# EP1C6T144I8N_2.net
KiCad netlist of a schematic drawn in Altium Designer
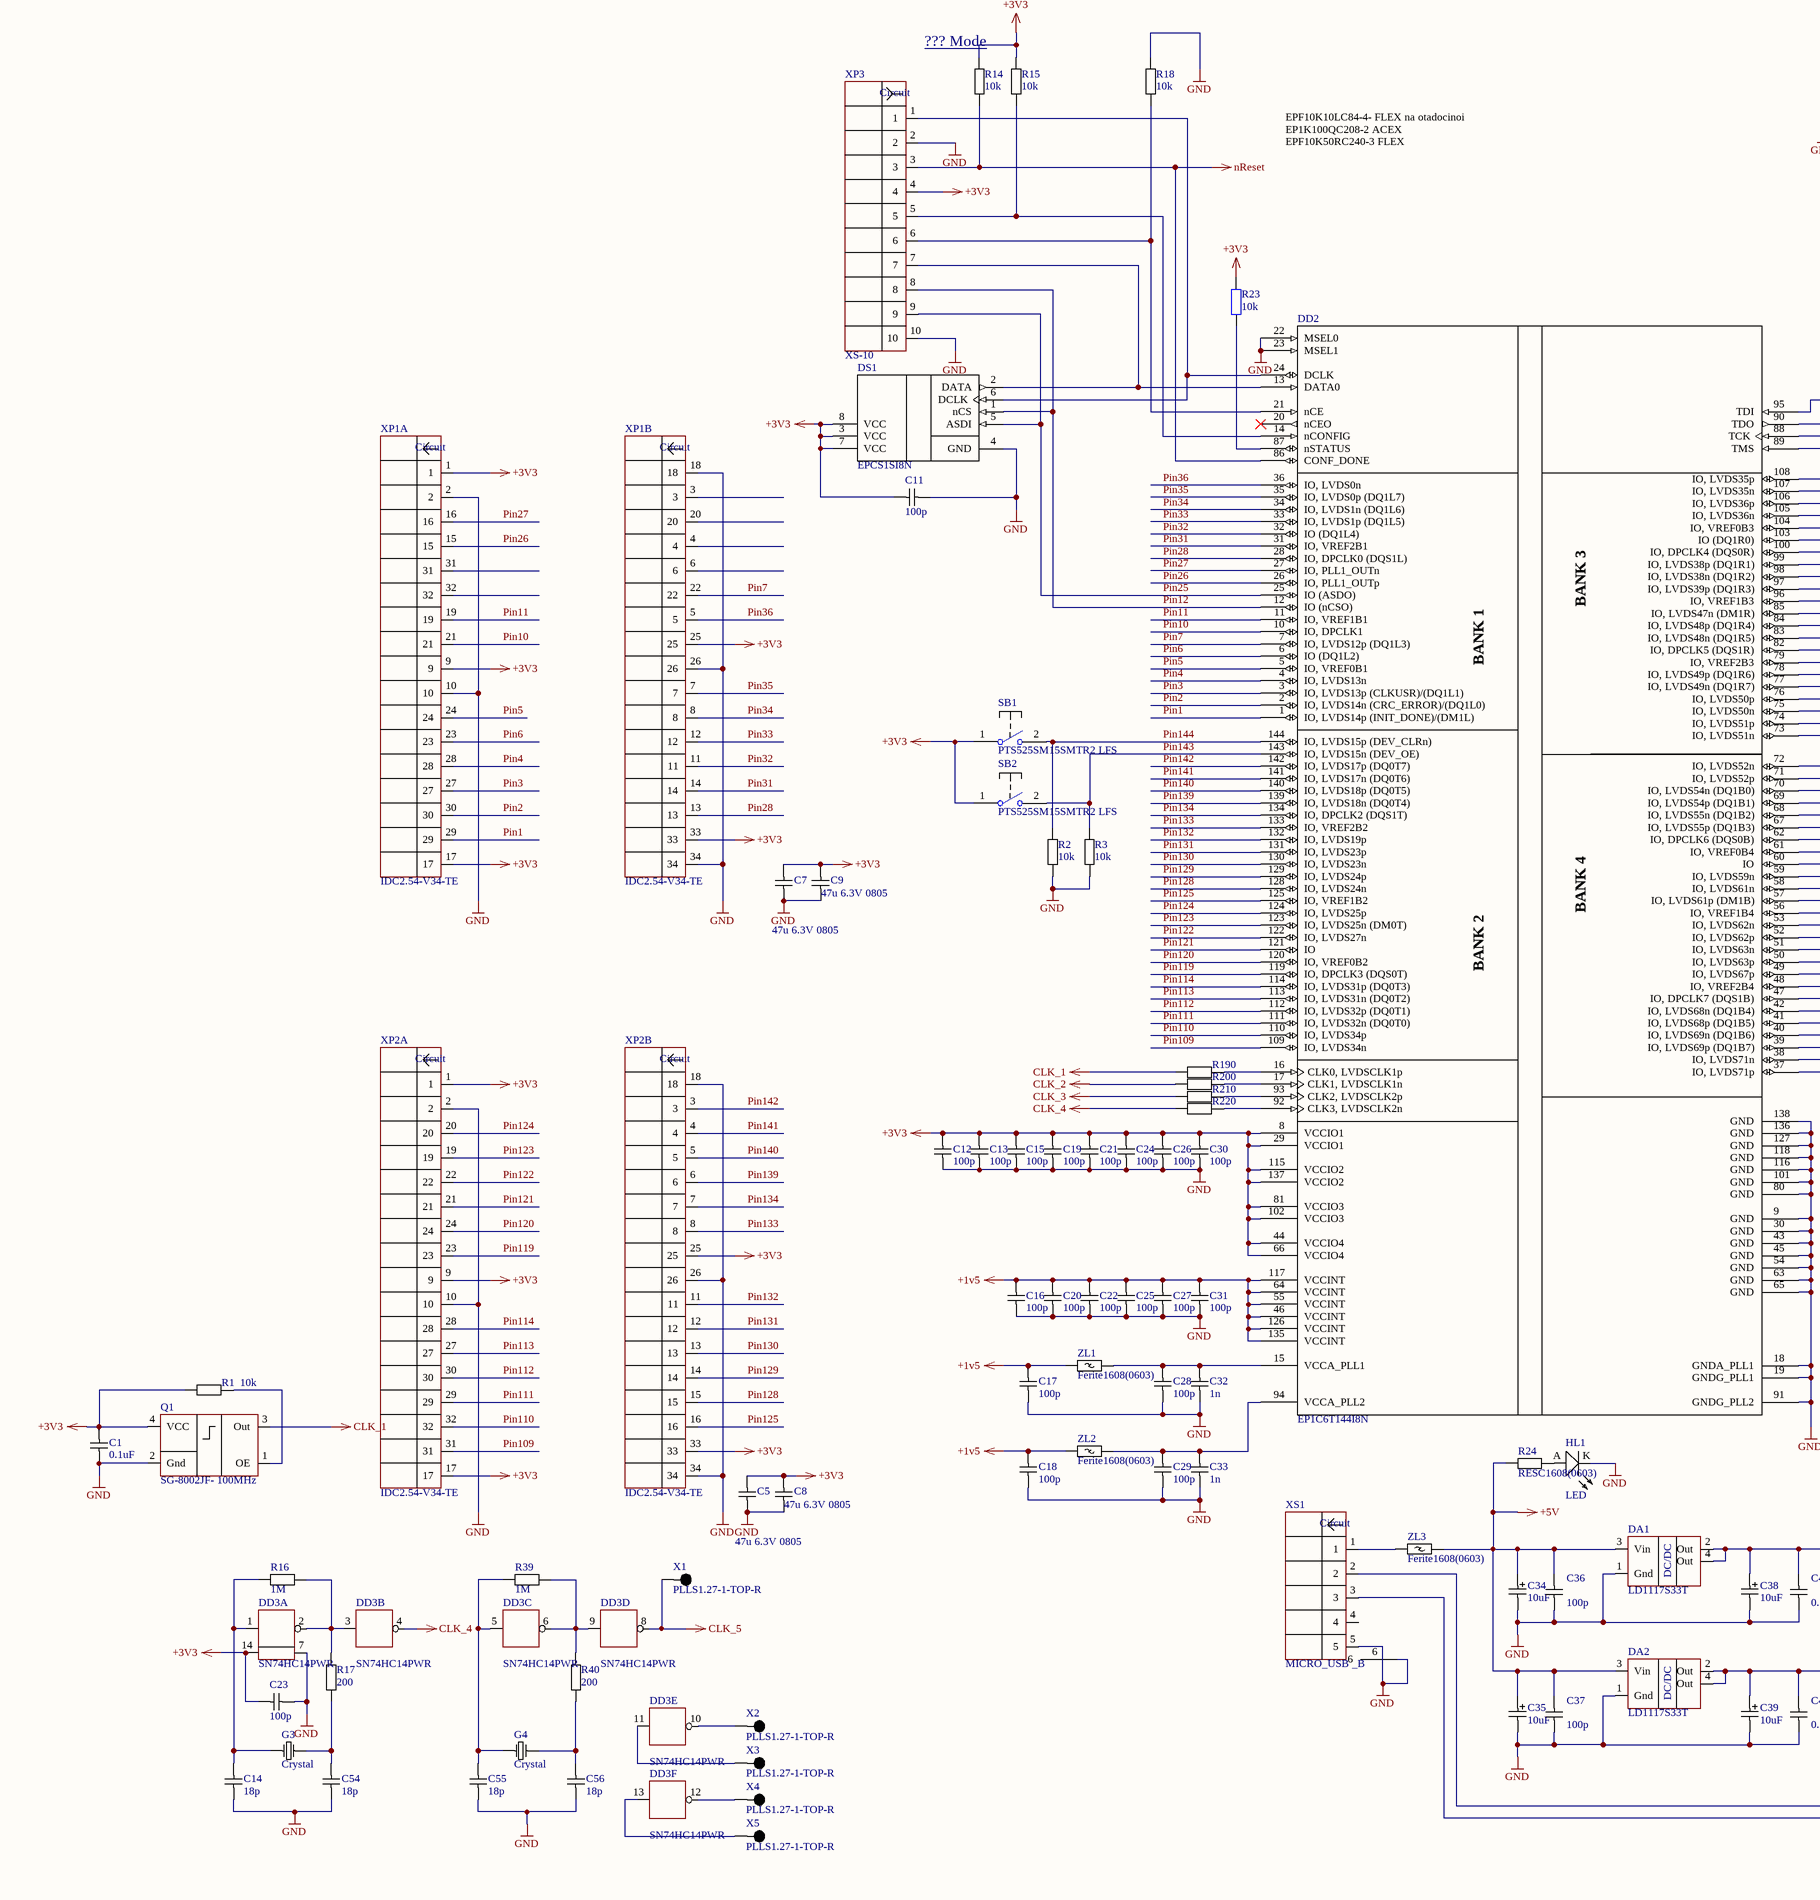
[diagram p0: EP1C6T144I8N (2).SchDoc, bottom left]
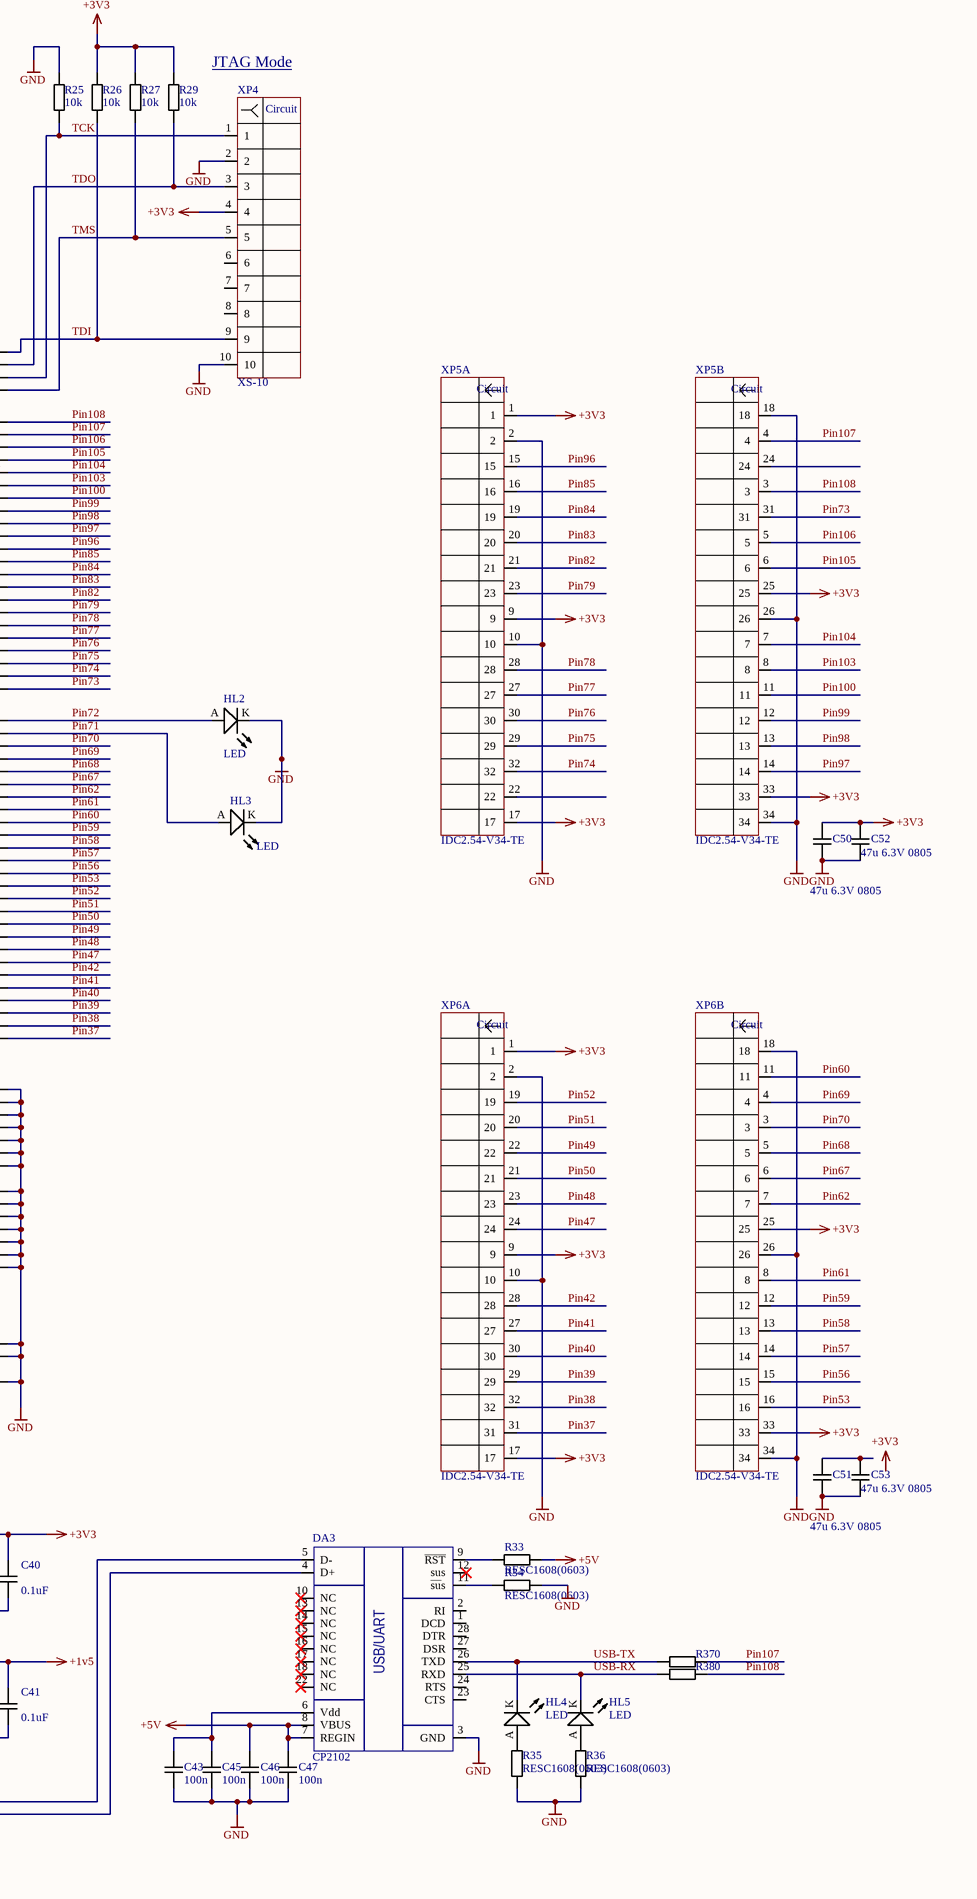
[diagram p1: EP1C6T144I8N (2).SchDoc, bottom right]

(export (version "E")
  (design (tool "Eeschema 10.0.6"))
  (components
    (comp (ref "C1")
      (value "0.1uF")
      (footprint "1005[0402]:CapKemet1005(0402)")
      (fields (field (name "PART NUMBER") "CAPC1005(0402)N") (field (name "DIGI-KEY PART NUMBER") "?"))
      (libsource (lib "ADdatabaseLibfile") (part "Cap"))
    )
    (comp (ref "C5")
      (value "47u 6.3V 0805")
      (footprint "CAPC2012(0805)N")
      (description "CAP CER 47UF 6.3V X5R 0805")
      (fields
        (field (name "PART NUMBER") "CAPC2012(0805)")
        (field (name "DIGI-KEY PART NUMBER") "490-13249-1-ND")
      )
      (libsource (lib "SssAccesDatbase") (part "Cap"))
    )
    (comp (ref "C7")
      (value "47u 6.3V 0805")
      (footprint "CAPC2012(0805)N")
      (description "CAP CER 47UF 6.3V X5R 0805")
      (fields
        (field (name "PART NUMBER") "CAPC2012(0805)")
        (field (name "DIGI-KEY PART NUMBER") "490-13249-1-ND")
      )
      (libsource (lib "SssAccesDatbase") (part "Cap"))
    )
    (comp (ref "C8")
      (value "47u 6.3V 0805")
      (footprint "CAPC2012(0805)N")
      (description "CAP CER 47UF 6.3V X5R 0805")
      (fields
        (field (name "PART NUMBER") "CAPC2012(0805)")
        (field (name "DIGI-KEY PART NUMBER") "490-13249-1-ND")
      )
      (libsource (lib "SssAccesDatbase") (part "Cap"))
    )
    (comp (ref "C9")
      (value "47u 6.3V 0805")
      (footprint "CAPC2012(0805)N")
      (description "CAP CER 47UF 6.3V X5R 0805")
      (fields
        (field (name "PART NUMBER") "CAPC2012(0805)")
        (field (name "DIGI-KEY PART NUMBER") "490-13249-1-ND")
      )
      (libsource (lib "SssAccesDatbase") (part "Cap"))
    )
    (comp (ref "C11")
      (value "100p")
      (footprint "1005[0402]:CapKemet1005(0402)")
      (fields (field (name "PART NUMBER") "CAPC1005(0402)N") (field (name "DIGI-KEY PART NUMBER") "?"))
      (libsource (lib "ADdatabaseLibfile") (part "Cap"))
    )
    (comp (ref "C12")
      (value "100p")
      (footprint "1005[0402]:CapKemet1005(0402)")
      (fields (field (name "PART NUMBER") "CAPC1005(0402)N") (field (name "DIGI-KEY PART NUMBER") "?"))
      (libsource (lib "ADdatabaseLibfile") (part "Cap"))
    )
    (comp (ref "C13")
      (value "100p")
      (footprint "1005[0402]:CapKemet1005(0402)")
      (fields (field (name "PART NUMBER") "CAPC1005(0402)N") (field (name "DIGI-KEY PART NUMBER") "?"))
      (libsource (lib "ADdatabaseLibfile") (part "Cap"))
    )
    (comp (ref "C14")
      (value "18p")
      (footprint "CAPC1608(0603)N")
      (description "?")
      (fields (field (name "PART NUMBER") "CAPC1608(0603)"))
      (libsource (lib "SssAccesDatbase") (part "Cap"))
    )
    (comp (ref "C15")
      (value "100p")
      (footprint "1005[0402]:CapKemet1005(0402)")
      (fields (field (name "PART NUMBER") "CAPC1005(0402)N") (field (name "DIGI-KEY PART NUMBER") "?"))
      (libsource (lib "ADdatabaseLibfile") (part "Cap"))
    )
    (comp (ref "C16")
      (value "100p")
      (footprint "1005[0402]:CapKemet1005(0402)")
      (fields (field (name "PART NUMBER") "CAPC1005(0402)N") (field (name "DIGI-KEY PART NUMBER") "?"))
      (libsource (lib "ADdatabaseLibfile") (part "Cap"))
    )
    (comp (ref "C17")
      (value "100p")
      (footprint "1005[0402]:CapKemet1005(0402)")
      (fields (field (name "PART NUMBER") "CAPC1005(0402)N") (field (name "DIGI-KEY PART NUMBER") "?"))
      (libsource (lib "ADdatabaseLibfile") (part "Cap"))
    )
    (comp (ref "C18")
      (value "100p")
      (footprint "1005[0402]:CapKemet1005(0402)")
      (fields (field (name "PART NUMBER") "CAPC1005(0402)N") (field (name "DIGI-KEY PART NUMBER") "?"))
      (libsource (lib "ADdatabaseLibfile") (part "Cap"))
    )
    (comp (ref "C19")
      (value "100p")
      (footprint "1005[0402]:CapKemet1005(0402)")
      (fields (field (name "PART NUMBER") "CAPC1005(0402)N") (field (name "DIGI-KEY PART NUMBER") "?"))
      (libsource (lib "ADdatabaseLibfile") (part "Cap"))
    )
    (comp (ref "C20")
      (value "100p")
      (footprint "1005[0402]:CapKemet1005(0402)")
      (fields (field (name "PART NUMBER") "CAPC1005(0402)N") (field (name "DIGI-KEY PART NUMBER") "?"))
      (libsource (lib "ADdatabaseLibfile") (part "Cap"))
    )
    (comp (ref "C21")
      (value "100p")
      (footprint "1005[0402]:CapKemet1005(0402)")
      (fields (field (name "PART NUMBER") "CAPC1005(0402)N") (field (name "DIGI-KEY PART NUMBER") "?"))
      (libsource (lib "ADdatabaseLibfile") (part "Cap"))
    )
    (comp (ref "C22")
      (value "100p")
      (footprint "1005[0402]:CapKemet1005(0402)")
      (fields (field (name "PART NUMBER") "CAPC1005(0402)N") (field (name "DIGI-KEY PART NUMBER") "?"))
      (libsource (lib "ADdatabaseLibfile") (part "Cap"))
    )
    (comp (ref "C23")
      (value "100p")
      (footprint "CAPC1608(0603)N")
      (description "?")
      (fields (field (name "PART NUMBER") "CAPC1608(0603)"))
      (libsource (lib "SssAccesDatbaseDYandex") (part "Cap"))
    )
    (comp (ref "C24")
      (value "100p")
      (footprint "1005[0402]:CapKemet1005(0402)")
      (fields (field (name "PART NUMBER") "CAPC1005(0402)N") (field (name "DIGI-KEY PART NUMBER") "?"))
      (libsource (lib "ADdatabaseLibfile") (part "Cap"))
    )
    (comp (ref "C25")
      (value "100p")
      (footprint "1005[0402]:CapKemet1005(0402)")
      (fields (field (name "PART NUMBER") "CAPC1005(0402)N") (field (name "DIGI-KEY PART NUMBER") "?"))
      (libsource (lib "ADdatabaseLibfile") (part "Cap"))
    )
    (comp (ref "C26")
      (value "100p")
      (footprint "1005[0402]:CapKemet1005(0402)")
      (fields (field (name "PART NUMBER") "CAPC1005(0402)N") (field (name "DIGI-KEY PART NUMBER") "?"))
      (libsource (lib "ADdatabaseLibfile") (part "Cap"))
    )
    (comp (ref "C27")
      (value "100p")
      (footprint "1005[0402]:CapKemet1005(0402)")
      (fields (field (name "PART NUMBER") "CAPC1005(0402)N") (field (name "DIGI-KEY PART NUMBER") "?"))
      (libsource (lib "ADdatabaseLibfile") (part "Cap"))
    )
    (comp (ref "C28")
      (value "100p")
      (footprint "1005[0402]:CapKemet1005(0402)")
      (fields (field (name "PART NUMBER") "CAPC1005(0402)N") (field (name "DIGI-KEY PART NUMBER") "?"))
      (libsource (lib "ADdatabaseLibfile") (part "Cap"))
    )
    (comp (ref "C29")
      (value "100p")
      (footprint "1005[0402]:CapKemet1005(0402)")
      (fields (field (name "PART NUMBER") "CAPC1005(0402)N") (field (name "DIGI-KEY PART NUMBER") "?"))
      (libsource (lib "ADdatabaseLibfile") (part "Cap"))
    )
    (comp (ref "C30")
      (value "100p")
      (footprint "1005[0402]:CapKemet1005(0402)")
      (fields (field (name "PART NUMBER") "CAPC1005(0402)N") (field (name "DIGI-KEY PART NUMBER") "?"))
      (libsource (lib "ADdatabaseLibfile") (part "Cap"))
    )
    (comp (ref "C31")
      (value "100p")
      (footprint "1005[0402]:CapKemet1005(0402)")
      (fields (field (name "PART NUMBER") "CAPC1005(0402)N") (field (name "DIGI-KEY PART NUMBER") "?"))
      (libsource (lib "ADdatabaseLibfile") (part "Cap"))
    )
    (comp (ref "C32")
      (value "1n")
      (footprint "1005[0402]:CapKemet1005(0402)")
      (fields (field (name "PART NUMBER") "CAPC1005(0402)N") (field (name "DIGI-KEY PART NUMBER") "?"))
      (libsource (lib "ADdatabaseLibfile") (part "Cap"))
    )
    (comp (ref "C33")
      (value "1n")
      (footprint "1005[0402]:CapKemet1005(0402)")
      (fields (field (name "PART NUMBER") "CAPC1005(0402)N") (field (name "DIGI-KEY PART NUMBER") "?"))
      (libsource (lib "ADdatabaseLibfile") (part "Cap"))
    )
    (comp (ref "C34")
      (value "10uF")
      (footprint "0402-A")
      (fields (field (name "PART NUMBER") "CapTantA"))
      (libsource (lib "ADdatabaseLibfile") (part "Cap Pol1"))
    )
    (comp (ref "C35")
      (value "10uF")
      (footprint "0402-A")
      (fields (field (name "PART NUMBER") "CapTantA"))
      (libsource (lib "ADdatabaseLibfile") (part "Cap Pol1"))
    )
    (comp (ref "C36")
      (value "100p")
      (footprint "1005[0402]:CapKemet1005(0402)")
      (fields (field (name "PART NUMBER") "CAPC1005(0402)N") (field (name "DIGI-KEY PART NUMBER") "?"))
      (libsource (lib "ADdatabaseLibfile") (part "Cap"))
    )
    (comp (ref "C37")
      (value "100p")
      (footprint "1005[0402]:CapKemet1005(0402)")
      (fields (field (name "PART NUMBER") "CAPC1005(0402)N") (field (name "DIGI-KEY PART NUMBER") "?"))
      (libsource (lib "ADdatabaseLibfile") (part "Cap"))
    )
    (comp (ref "C38")
      (value "10uF")
      (footprint "0402-A")
      (fields (field (name "PART NUMBER") "CapTantA"))
      (libsource (lib "ADdatabaseLibfile") (part "Cap Pol1"))
    )
    (comp (ref "C39")
      (value "10uF")
      (footprint "0402-A")
      (fields (field (name "PART NUMBER") "CapTantA"))
      (libsource (lib "ADdatabaseLibfile") (part "Cap Pol1"))
    )
    (comp (ref "C40")
      (value "0.1uF")
      (footprint "1005[0402]:CapKemet1005(0402)")
      (fields (field (name "PART NUMBER") "CAPC1005(0402)N") (field (name "DIGI-KEY PART NUMBER") "?"))
      (libsource (lib "ADdatabaseLibfile") (part "Cap"))
    )
    (comp (ref "C41")
      (value "0.1uF")
      (footprint "1005[0402]:CapKemet1005(0402)")
      (fields (field (name "PART NUMBER") "CAPC1005(0402)N") (field (name "DIGI-KEY PART NUMBER") "?"))
      (libsource (lib "ADdatabaseLibfile") (part "Cap"))
    )
    (comp (ref "C43")
      (value "100n")
      (footprint "CAPC1608(0603)N")
      (description "?")
      (fields (field (name "PART NUMBER") "CAPC1608(0603)"))
      (libsource (lib "SssAccesDatbase") (part "Cap"))
    )
    (comp (ref "C45")
      (value "100n")
      (footprint "CAPC1608(0603)N")
      (description "?")
      (fields (field (name "PART NUMBER") "CAPC1608(0603)"))
      (libsource (lib "SssAccesDatbase") (part "Cap"))
    )
    (comp (ref "C46")
      (value "100n")
      (footprint "CAPC1608(0603)N")
      (description "?")
      (fields (field (name "PART NUMBER") "CAPC1608(0603)"))
      (libsource (lib "SssAccesDatbase") (part "Cap"))
    )
    (comp (ref "C47")
      (value "100n")
      (footprint "CAPC1608(0603)N")
      (description "?")
      (fields (field (name "PART NUMBER") "CAPC1608(0603)"))
      (libsource (lib "SssAccesDatbase") (part "Cap"))
    )
    (comp (ref "C50")
      (value "47u 6.3V 0805")
      (footprint "CAPC2012(0805)N")
      (description "CAP CER 47UF 6.3V X5R 0805")
      (fields
        (field (name "PART NUMBER") "CAPC2012(0805)")
        (field (name "DIGI-KEY PART NUMBER") "490-13249-1-ND")
      )
      (libsource (lib "SssAccesDatbase") (part "Cap"))
    )
    (comp (ref "C51")
      (value "47u 6.3V 0805")
      (footprint "CAPC2012(0805)N")
      (description "CAP CER 47UF 6.3V X5R 0805")
      (fields
        (field (name "PART NUMBER") "CAPC2012(0805)")
        (field (name "DIGI-KEY PART NUMBER") "490-13249-1-ND")
      )
      (libsource (lib "SssAccesDatbase") (part "Cap"))
    )
    (comp (ref "C52")
      (value "47u 6.3V 0805")
      (footprint "CAPC2012(0805)N")
      (description "CAP CER 47UF 6.3V X5R 0805")
      (fields
        (field (name "PART NUMBER") "CAPC2012(0805)")
        (field (name "DIGI-KEY PART NUMBER") "490-13249-1-ND")
      )
      (libsource (lib "SssAccesDatbase") (part "Cap"))
    )
    (comp (ref "C53")
      (value "47u 6.3V 0805")
      (footprint "CAPC2012(0805)N")
      (description "CAP CER 47UF 6.3V X5R 0805")
      (fields
        (field (name "PART NUMBER") "CAPC2012(0805)")
        (field (name "DIGI-KEY PART NUMBER") "490-13249-1-ND")
      )
      (libsource (lib "SssAccesDatbase") (part "Cap"))
    )
    (comp (ref "C54")
      (value "18p")
      (footprint "CAPC1608(0603)N")
      (description "?")
      (fields (field (name "PART NUMBER") "CAPC1608(0603)"))
      (libsource (lib "SssAccesDatbase") (part "Cap"))
    )
    (comp (ref "C55")
      (value "18p")
      (footprint "CAPC1608(0603)N")
      (description "?")
      (fields (field (name "PART NUMBER") "CAPC1608(0603)"))
      (libsource (lib "SssAccesDatbase") (part "Cap"))
    )
    (comp (ref "C56")
      (value "18p")
      (footprint "CAPC1608(0603)N")
      (description "?")
      (fields (field (name "PART NUMBER") "CAPC1608(0603)"))
      (libsource (lib "SssAccesDatbase") (part "Cap"))
    )
    (comp (ref "DA1")
      (value "LD1117S33T")
      (footprint "SOT223_M")
      (libsource (lib "ADdatabaseLibfile") (part "LD1117S33T"))
    )
    (comp (ref "DA2")
      (value "LD1117S33T")
      (footprint "SOT223_M")
      (libsource (lib "ADdatabaseLibfile") (part "LD1117S33T"))
    )
    (comp (ref "DA3")
      (value "CP2102")
      (footprint "QFN28")
      (libsource (lib "SssAccesDatbaseDYandex") (part "CP2102"))
    )
    (comp (ref "DD2")
      (value "EP1C6T144I8N")
      (footprint "TQFP144_N")
      (fields (field (name "PUBLISHER") "Altium Limited"))
      (libsource (lib "SssAccesDatbase") (part "EP1C6T144I8N"))
    )
    (comp (ref "DD3")
      (value "SN74HC14PWR")
      (footprint "TSSOP14")
      (description "IC INVERTER SCHMITT 6CH 14TSSOP")
      (libsource (lib "SssAccesDatbase") (part "74HC14"))
    )
    (comp (ref "DS1")
      (value "EPCS1SI8N")
      (footprint "SO8_N")
      (description "IC CONFIG DEVICE 1MBIT 8SOIC")
      (fields (field (name "PUBLISHER") "Altium Limited"))
      (libsource (lib "SssAccesDatbase") (part "EPCS1SI8N"))
    )
    (comp (ref "G3")
      (value "Crystal")
      (footprint "HC-49/S")
      (description "Crystal HC-49/S")
      (libsource (lib "SssAccesDatbaseDYandex") (part "Crystal"))
    )
    (comp (ref "G4")
      (value "Crystal")
      (footprint "HC-49/S")
      (description "Crystal HC-49/S")
      (libsource (lib "SssAccesDatbaseDYandex") (part "Crystal"))
    )
    (comp (ref "HL1")
      (value "LED")
      (footprint "LED-0603-GREEN")
      (description "LED GREEN DIFFUSED 0603 SMD")
      (fields
        (field (name "PART NUMBER") "LED-0603-GREEN")
        (field (name "DIGI-KEY PART NUMBER") "732-12017-1-ND")
      )
      (libsource (lib "SssAccesDatbase") (part "LED"))
    )
    (comp (ref "HL2")
      (value "LED")
      (footprint "LED-0603-GREEN")
      (description "LED GREEN DIFFUSED 0603 SMD")
      (fields
        (field (name "PART NUMBER") "LED-0603-GREEN")
        (field (name "DIGI-KEY PART NUMBER") "732-12017-1-ND")
      )
      (libsource (lib "SssAccesDatbase") (part "LED"))
    )
    (comp (ref "HL3")
      (value "LED")
      (footprint "LED-0603-BLUE")
      (description "LED BLUE DIFFUSED 0603 SMD")
      (fields
        (field (name "PART NUMBER") "LED-0603-BLUE")
        (field (name "DIGI-KEY PART NUMBER") "732-12013-1-ND")
      )
      (libsource (lib "SssAccesDatbase") (part "LED"))
    )
    (comp (ref "HL4")
      (value "LED")
      (footprint "LED-0603-BLUE")
      (description "LED BLUE DIFFUSED 0603 SMD")
      (fields
        (field (name "PART NUMBER") "LED-0603-BLUE")
        (field (name "DIGI-KEY PART NUMBER") "732-12013-1-ND")
      )
      (libsource (lib "SssAccesDatbase") (part "LED"))
    )
    (comp (ref "HL5")
      (value "LED")
      (footprint "LED-0603-GREEN")
      (description "LED GREEN DIFFUSED 0603 SMD")
      (fields
        (field (name "PART NUMBER") "LED-0603-GREEN")
        (field (name "DIGI-KEY PART NUMBER") "732-12017-1-ND")
      )
      (libsource (lib "SssAccesDatbase") (part "LED"))
    )
    (comp (ref "Q1")
      (value "SG-8002JF- 100MHz")
      (footprint "SG-8002JF")
      (fields (field (name "PART NUMBER") "SG-8002JF"))
      (libsource (lib "ADdatabaseLibfile") (part "SG-8002JF"))
    )
    (comp (ref "R1")
      (value "10k")
      (footprint "1005[0402]:REZKemet 0402")
      (fields (field (name "PART NUMBER") "RESC1005(0402)") (field (name "DIGI-KEY PART NUMBER") "???"))
      (libsource (lib "") (part "Resistor general_1"))
    )
    (comp (ref "R2")
      (value "10k")
      (footprint "1005[0402]:REZKemet 0402")
      (fields (field (name "PART NUMBER") "RESC1005(0402)") (field (name "DIGI-KEY PART NUMBER") "???"))
      (libsource (lib "SssAccesDatbaseDYandex") (part "Resistor general"))
    )
    (comp (ref "R3")
      (value "10k")
      (footprint "1005[0402]:REZKemet 0402")
      (fields (field (name "PART NUMBER") "RESC1005(0402)") (field (name "DIGI-KEY PART NUMBER") "???"))
      (libsource (lib "SssAccesDatbaseDYandex") (part "Resistor general"))
    )
    (comp (ref "R14")
      (value "10k")
      (footprint "1005[0402]:REZKemet 0402")
      (fields (field (name "PART NUMBER") "RESC1005(0402)") (field (name "DIGI-KEY PART NUMBER") "???"))
      (libsource (lib "SssAccesDatbaseDYandex") (part "Resistor general"))
    )
    (comp (ref "R15")
      (value "10k")
      (footprint "1005[0402]:REZKemet 0402")
      (fields (field (name "PART NUMBER") "RESC1005(0402)") (field (name "DIGI-KEY PART NUMBER") "???"))
      (libsource (lib "SssAccesDatbaseDYandex") (part "Resistor general"))
    )
    (comp (ref "R16")
      (value "1M")
      (footprint "RESC1608(0603)N")
      (fields (field (name "PART NUMBER") "RESC1608(0603)") (field (name "DIGI-KEY PART NUMBER") "???"))
      (libsource (lib "") (part "Resistor general_1"))
    )
    (comp (ref "R17")
      (value "200")
      (footprint "RESC1608(0603)N")
      (fields (field (name "PART NUMBER") "RESC1608(0603)") (field (name "DIGI-KEY PART NUMBER") "???"))
      (libsource (lib "SssAccesDatbaseDYandex") (part "Resistor general"))
    )
    (comp (ref "R18")
      (value "10k")
      (footprint "1005[0402]:REZKemet 0402")
      (fields (field (name "PART NUMBER") "RESC1005(0402)") (field (name "DIGI-KEY PART NUMBER") "???"))
      (libsource (lib "SssAccesDatbaseDYandex") (part "Resistor general"))
    )
    (comp (ref "R19")
      (value "0")
      (footprint "RESC1608(0603)N")
      (fields (field (name "PART NUMBER") "RESC1608(0603)") (field (name "DIGI-KEY PART NUMBER") "???"))
      (libsource (lib "") (part "Resistor general_1"))
    )
    (comp (ref "R20")
      (value "0")
      (footprint "RESC1608(0603)N")
      (fields (field (name "PART NUMBER") "RESC1608(0603)") (field (name "DIGI-KEY PART NUMBER") "???"))
      (libsource (lib "") (part "Resistor general_1"))
    )
    (comp (ref "R21")
      (value "0")
      (footprint "RESC1608(0603)N")
      (fields (field (name "PART NUMBER") "RESC1608(0603)") (field (name "DIGI-KEY PART NUMBER") "???"))
      (libsource (lib "") (part "Resistor general_1"))
    )
    (comp (ref "R22")
      (value "0")
      (footprint "RESC1608(0603)N")
      (fields (field (name "PART NUMBER") "RESC1608(0603)") (field (name "DIGI-KEY PART NUMBER") "???"))
      (libsource (lib "") (part "Resistor general_1"))
    )
    (comp (ref "R23")
      (value "10k")
      (footprint "1005[0402]:REZKemet 0402")
      (description "Resistor")
      (fields (field (name "PART NUMBER") "RESC1005(0402)") (field (name "DIGI-KEY PART NUMBER") "???"))
      (libsource (lib "ADdatabaseLibfile") (part "Res2"))
    )
    (comp (ref "R24")
      (value "RESC1608(0603)")
      (footprint "RESC1608(0603)N")
      (fields (field (name "DIGI-KEY PART NUMBER") "???"))
      (libsource (lib "") (part "Resistor general_3"))
    )
    (comp (ref "R25")
      (value "10k")
      (footprint "1005[0402]:REZKemet 0402")
      (fields (field (name "PART NUMBER") "RESC1005(0402)") (field (name "DIGI-KEY PART NUMBER") "???"))
      (libsource (lib "SssAccesDatbaseDYandex") (part "Resistor general"))
    )
    (comp (ref "R26")
      (value "10k")
      (footprint "1005[0402]:REZKemet 0402")
      (fields (field (name "PART NUMBER") "RESC1005(0402)") (field (name "DIGI-KEY PART NUMBER") "???"))
      (libsource (lib "SssAccesDatbaseDYandex") (part "Resistor general"))
    )
    (comp (ref "R27")
      (value "10k")
      (footprint "1005[0402]:REZKemet 0402")
      (fields (field (name "PART NUMBER") "RESC1005(0402)") (field (name "DIGI-KEY PART NUMBER") "???"))
      (libsource (lib "SssAccesDatbaseDYandex") (part "Resistor general"))
    )
    (comp (ref "R29")
      (value "10k")
      (footprint "1005[0402]:REZKemet 0402")
      (fields (field (name "PART NUMBER") "RESC1005(0402)") (field (name "DIGI-KEY PART NUMBER") "???"))
      (libsource (lib "SssAccesDatbaseDYandex") (part "Resistor general"))
    )
    (comp (ref "R33")
      (value "RESC1608(0603)")
      (footprint "RESC1608(0603)N")
      (fields (field (name "DIGI-KEY PART NUMBER") "???"))
      (libsource (lib "") (part "Resistor general_1"))
    )
    (comp (ref "R34")
      (value "RESC1608(0603)")
      (footprint "RESC1608(0603)N")
      (fields (field (name "DIGI-KEY PART NUMBER") "???"))
      (libsource (lib "") (part "Resistor general_3"))
    )
    (comp (ref "R35")
      (value "RESC1608(0603)")
      (footprint "RESC1608(0603)N")
      (fields (field (name "DIGI-KEY PART NUMBER") "???"))
      (libsource (lib "") (part "Resistor general_2"))
    )
    (comp (ref "R36")
      (value "RESC1608(0603)")
      (footprint "RESC1608(0603)N")
      (fields (field (name "DIGI-KEY PART NUMBER") "???"))
      (libsource (lib "") (part "Resistor general_2"))
    )
    (comp (ref "R37")
      (value "0")
      (footprint "RESC1608(0603)N")
      (fields (field (name "PART NUMBER") "RESC1608(0603)") (field (name "DIGI-KEY PART NUMBER") "???"))
      (libsource (lib "") (part "Resistor general_1"))
    )
    (comp (ref "R38")
      (value "0")
      (footprint "RESC1608(0603)N")
      (fields (field (name "PART NUMBER") "RESC1608(0603)") (field (name "DIGI-KEY PART NUMBER") "???"))
      (libsource (lib "") (part "Resistor general_1"))
    )
    (comp (ref "R39")
      (value "1M")
      (footprint "RESC1608(0603)N")
      (fields (field (name "PART NUMBER") "RESC1608(0603)") (field (name "DIGI-KEY PART NUMBER") "???"))
      (libsource (lib "") (part "Resistor general_1"))
    )
    (comp (ref "R40")
      (value "200")
      (footprint "RESC1608(0603)N")
      (fields (field (name "PART NUMBER") "RESC1608(0603)") (field (name "DIGI-KEY PART NUMBER") "???"))
      (libsource (lib "SssAccesDatbaseDYandex") (part "Resistor general"))
    )
    (comp (ref "SB1")
      (value "PTS525SM15SMTR2 LFS")
      (footprint "TACT_SWITCH KPT1187B")
      (description "SWITCH TACTILE SPST-NO 0.02A 15V")
      (fields (field (name "DIGI-KEY PART NUMBER") "CKN9104CT-ND"))
      (libsource (lib "SssAccesDatbase") (part "TACT_SWITCH KPT1187B"))
    )
    (comp (ref "SB2")
      (value "PTS525SM15SMTR2 LFS")
      (footprint "TACT_SWITCH KPT1187B")
      (description "SWITCH TACTILE SPST-NO 0.02A 15V")
      (fields (field (name "DIGI-KEY PART NUMBER") "CKN9104CT-ND"))
      (libsource (lib "SssAccesDatbase") (part "TACT_SWITCH KPT1187B"))
    )
    (comp (ref "X1")
      (value "PLLS1.27-1-TOP-R")
      (footprint "PLLS1.27-1-TOP-R")
      (libsource (lib "SssAccesDatbase") (part "X1_1"))
    )
    (comp (ref "X2")
      (value "PLLS1.27-1-TOP-R")
      (footprint "PLLS1.27-1-TOP-R")
      (libsource (lib "SssAccesDatbase") (part "X1_1"))
    )
    (comp (ref "X3")
      (value "PLLS1.27-1-TOP-R")
      (footprint "PLLS1.27-1-TOP-R")
      (libsource (lib "SssAccesDatbase") (part "X1_1"))
    )
    (comp (ref "X4")
      (value "PLLS1.27-1-TOP-R")
      (footprint "PLLS1.27-1-TOP-R")
      (libsource (lib "SssAccesDatbase") (part "X1_1"))
    )
    (comp (ref "X5")
      (value "PLLS1.27-1-TOP-R")
      (footprint "PLLS1.27-1-TOP-R")
      (libsource (lib "SssAccesDatbase") (part "X1_1"))
    )
    (comp (ref "XP1")
      (value "IDC2.54-V34-TE")
      (footprint "IDC2.54-V34-TE")
      (libsource (lib "") (part "XP-34_2"))
    )
    (comp (ref "XP2")
      (value "IDC2.54-V34-TE")
      (footprint "IDC2.54-V34-TE")
      (libsource (lib "") (part "XP-34_5"))
    )
    (comp (ref "XP3")
      (value "XS-10")
      (footprint "BH-10")
      (fields
        (field (name "PART NUMBER") "3220-10-0100-00")
        (field (name "DIGI-KEY PART NUMBER") "1175-1627-ND")
      )
      (libsource (lib "ADdatabaseLibfile") (part "XS-10"))
    )
    (comp (ref "XP4")
      (value "XS-10")
      (footprint "BH-10")
      (fields
        (field (name "PART NUMBER") "3220-10-0100-00")
        (field (name "DIGI-KEY PART NUMBER") "1175-1627-ND")
      )
      (libsource (lib "") (part "XS-10_1"))
    )
    (comp (ref "XP5")
      (value "IDC2.54-V34-TE")
      (footprint "IDC2.54-V34-TE")
      (libsource (lib "") (part "XP-34_1"))
    )
    (comp (ref "XP6")
      (value "IDC2.54-V34-TE")
      (footprint "IDC2.54-V34-TE")
      (libsource (lib "") (part "XP-34_7"))
    )
    (comp (ref "XS1")
      (value "MICRO_USB _B")
      (footprint "MICRO_USB _B")
      (fields (field (name "DIGI-KEY PART NUMBER") "???"))
      (libsource (lib "SssAccesDatbase") (part "Micro USB"))
    )
    (comp (ref "ZL1")
      (value "Ferite1608(0603)")
      (footprint "INDC1608(0603)N")
      (description "ferite bead")
      (fields (field (name "DIGI-KEY PART NUMBER") "???"))
      (libsource (lib "SssAccesDatbase") (part "ZL"))
    )
    (comp (ref "ZL2")
      (value "Ferite1608(0603)")
      (footprint "INDC1608(0603)N")
      (description "ferite bead")
      (fields (field (name "DIGI-KEY PART NUMBER") "???"))
      (libsource (lib "SssAccesDatbase") (part "ZL"))
    )
    (comp (ref "ZL3")
      (value "Ferite1608(0603)")
      (footprint "INDC1608(0603)N")
      (description "ferite bead")
      (fields (field (name "DIGI-KEY PART NUMBER") "???"))
      (libsource (lib "SssAccesDatbase") (part "ZL"))
    )
  )
  (nets
    (net (code "1") (name "+1v5") (class "Default")
      (node (ref "C16") (pin "1") (pinfunction "1_1") (pintype "passive"))
      (node (ref "C17") (pin "1") (pinfunction "1_1") (pintype "passive"))
      (node (ref "C18") (pin "1") (pinfunction "1_1") (pintype "passive"))
      (node (ref "C20") (pin "1") (pinfunction "1_1") (pintype "passive"))
      (node (ref "C22") (pin "1") (pinfunction "1_1") (pintype "passive"))
      (node (ref "C25") (pin "1") (pinfunction "1_1") (pintype "passive"))
      (node (ref "C27") (pin "1") (pinfunction "1_1") (pintype "passive"))
      (node (ref "C31") (pin "1") (pinfunction "1_1") (pintype "passive"))
      (node (ref "C39") (pin "1") (pinfunction "1_1") (pintype "passive"))
      (node (ref "C41") (pin "2") (pinfunction "2_2") (pintype "passive"))
      (node (ref "DA2") (pin "2") (pinfunction "Out_2") (pintype "passive"))
      (node (ref "DA2") (pin "4") (pinfunction "Out_4") (pintype "passive"))
      (node (ref "DD2") (pin "117") (pinfunction "VCCINT_117") (pintype "power_in"))
      (node (ref "DD2") (pin "126") (pinfunction "VCCINT_126") (pintype "power_in"))
      (node (ref "DD2") (pin "135") (pinfunction "VCCINT_135") (pintype "power_in"))
      (node (ref "DD2") (pin "46") (pinfunction "VCCINT_46") (pintype "power_in"))
      (node (ref "DD2") (pin "55") (pinfunction "VCCINT_55") (pintype "power_in"))
      (node (ref "DD2") (pin "64") (pinfunction "VCCINT_64") (pintype "power_in"))
      (node (ref "ZL1") (pin "1") (pinfunction "1_1") (pintype "passive"))
      (node (ref "ZL2") (pin "1") (pinfunction "1_1") (pintype "passive"))
    )
    (net (code "2") (name "+3V3") (class "Default")
      (node (ref "C1") (pin "2") (pinfunction "2_2") (pintype "passive"))
      (node (ref "C11") (pin "2") (pinfunction "2_2") (pintype "passive"))
      (node (ref "C12") (pin "1") (pinfunction "1_1") (pintype "passive"))
      (node (ref "C13") (pin "1") (pinfunction "1_1") (pintype "passive"))
      (node (ref "C15") (pin "1") (pinfunction "1_1") (pintype "passive"))
      (node (ref "C19") (pin "1") (pinfunction "1_1") (pintype "passive"))
      (node (ref "C21") (pin "1") (pinfunction "1_1") (pintype "passive"))
      (node (ref "C23") (pin "1") (pinfunction "1_1") (pintype "passive"))
      (node (ref "C24") (pin "1") (pinfunction "1_1") (pintype "passive"))
      (node (ref "C26") (pin "1") (pinfunction "1_1") (pintype "passive"))
      (node (ref "C30") (pin "1") (pinfunction "1_1") (pintype "passive"))
      (node (ref "C38") (pin "1") (pinfunction "1_1") (pintype "passive"))
      (node (ref "C40") (pin "2") (pinfunction "2_2") (pintype "passive"))
      (node (ref "C5") (pin "2") (pinfunction "2_2") (pintype "passive"))
      (node (ref "C50") (pin "2") (pinfunction "2_2") (pintype "passive"))
      (node (ref "C52") (pin "2") (pinfunction "2_2") (pintype "passive"))
      (node (ref "C7") (pin "2") (pinfunction "2_2") (pintype "passive"))
      (node (ref "C8") (pin "2") (pinfunction "2_2") (pintype "passive"))
      (node (ref "C9") (pin "2") (pinfunction "2_2") (pintype "passive"))
      (node (ref "DA1") (pin "2") (pinfunction "Out_2") (pintype "passive"))
      (node (ref "DA1") (pin "4") (pinfunction "Out_4") (pintype "passive"))
      (node (ref "DD2") (pin "102") (pinfunction "VCCIO3_102") (pintype "power_in"))
      (node (ref "DD2") (pin "115") (pinfunction "VCCIO2_115") (pintype "power_in"))
      (node (ref "DD2") (pin "137") (pinfunction "VCCIO2_137") (pintype "power_in"))
      (node (ref "DD2") (pin "29") (pinfunction "VCCIO1_29") (pintype "power_in"))
      (node (ref "DD2") (pin "44") (pinfunction "VCCIO4_44") (pintype "power_in"))
      (node (ref "DD2") (pin "66") (pinfunction "VCCIO4_66") (pintype "power_in"))
      (node (ref "DD2") (pin "8") (pinfunction "VCCIO1_8") (pintype "power_in"))
      (node (ref "DD2") (pin "81") (pinfunction "VCCIO3_81") (pintype "power_in"))
      (node (ref "DD3") (pin "14") (pinfunction "VCC_14") (pintype "power_in"))
      (node (ref "DS1") (pin "3") (pinfunction "VCC_3") (pintype "power_in"))
      (node (ref "DS1") (pin "7") (pinfunction "VCC_7") (pintype "power_in"))
      (node (ref "DS1") (pin "8") (pinfunction "VCC_8") (pintype "power_in"))
      (node (ref "Q1") (pin "4") (pinfunction "VCC_4") (pintype "passive"))
      (node (ref "R1") (pin "1") (pinfunction "1_1") (pintype "passive"))
      (node (ref "R14") (pin "2") (pinfunction "2_2") (pintype "passive"))
      (node (ref "R15") (pin "2") (pinfunction "2_2") (pintype "passive"))
      (node (ref "R23") (pin "2") (pinfunction "2_2") (pintype "passive"))
      (node (ref "R26") (pin "2") (pinfunction "2_2") (pintype "passive"))
      (node (ref "R27") (pin "2") (pinfunction "2_2") (pintype "passive"))
      (node (ref "R29") (pin "2") (pinfunction "2_2") (pintype "passive"))
      (node (ref "SB1") (pin "1") (pinfunction "COMMON_1") (pintype "passive"))
      (node (ref "SB2") (pin "1") (pinfunction "COMMON_1") (pintype "passive"))
      (node (ref "XP1") (pin "1") (pinfunction "1_1") (pintype "passive"))
      (node (ref "XP1") (pin "17") (pinfunction "17_17") (pintype "passive"))
      (node (ref "XP1") (pin "25") (pinfunction "25_25") (pintype "passive"))
      (node (ref "XP1") (pin "33") (pinfunction "33_33") (pintype "passive"))
      (node (ref "XP1") (pin "9") (pinfunction "9_9") (pintype "passive"))
      (node (ref "XP2") (pin "1") (pinfunction "1_1") (pintype "passive"))
      (node (ref "XP2") (pin "17") (pinfunction "17_17") (pintype "passive"))
      (node (ref "XP2") (pin "25") (pinfunction "25_25") (pintype "passive"))
      (node (ref "XP2") (pin "33") (pinfunction "33_33") (pintype "passive"))
      (node (ref "XP2") (pin "9") (pinfunction "9_9") (pintype "passive"))
      (node (ref "XP3") (pin "4") (pinfunction "4_4") (pintype "passive"))
      (node (ref "XP4") (pin "4") (pinfunction "4_4") (pintype "passive"))
      (node (ref "XP5") (pin "1") (pinfunction "1_1") (pintype "passive"))
      (node (ref "XP5") (pin "17") (pinfunction "17_17") (pintype "passive"))
      (node (ref "XP5") (pin "25") (pinfunction "25_25") (pintype "passive"))
      (node (ref "XP5") (pin "33") (pinfunction "33_33") (pintype "passive"))
      (node (ref "XP5") (pin "9") (pinfunction "9_9") (pintype "passive"))
      (node (ref "XP6") (pin "1") (pinfunction "1_1") (pintype "passive"))
      (node (ref "XP6") (pin "17") (pinfunction "17_17") (pintype "passive"))
      (node (ref "XP6") (pin "25") (pinfunction "25_25") (pintype "passive"))
      (node (ref "XP6") (pin "33") (pinfunction "33_33") (pintype "passive"))
      (node (ref "XP6") (pin "9") (pinfunction "9_9") (pintype "passive"))
    )
    (net (code "3") (name "+5V") (class "Default")
      (node (ref "C34") (pin "1") (pinfunction "1_1") (pintype "passive"))
      (node (ref "C35") (pin "1") (pinfunction "1_1") (pintype "passive"))
      (node (ref "C36") (pin "2") (pinfunction "2_2") (pintype "passive"))
      (node (ref "C37") (pin "2") (pinfunction "2_2") (pintype "passive"))
      (node (ref "C46") (pin "2") (pinfunction "2_2") (pintype "passive"))
      (node (ref "C47") (pin "2") (pinfunction "2_2") (pintype "passive"))
      (node (ref "DA1") (pin "3") (pinfunction "Vin_3") (pintype "passive"))
      (node (ref "DA2") (pin "3") (pinfunction "Vin_3") (pintype "passive"))
      (node (ref "DA3") (pin "7") (pinfunction "REGIN_7") (pintype "passive"))
      (node (ref "DA3") (pin "8") (pinfunction "VBUS_8") (pintype "passive"))
      (node (ref "R24") (pin "2") (pinfunction "2_2") (pintype "passive"))
      (node (ref "R33") (pin "2") (pinfunction "2_2") (pintype "passive"))
      (node (ref "ZL3") (pin "2") (pinfunction "2_2") (pintype "passive"))
    )
    (net (code "4") (name "/Pin1") (class "Default")
      (node (ref "DD2") (pin "1") (pinfunction "IO,_LVDS14p_(INIT_DONE)/(DM1L)_1") (pintype "bidirectional"))
      (node (ref "XP1") (pin "29") (pinfunction "29_29") (pintype "passive"))
    )
    (net (code "5") (name "/Pin2") (class "Default")
      (node (ref "DD2") (pin "2") (pinfunction "IO,_LVDS14n_(CRC_ERROR)/(DQ1L0)_2") (pintype "bidirectional"))
      (node (ref "XP1") (pin "30") (pinfunction "30_30") (pintype "passive"))
    )
    (net (code "6") (name "/Pin3") (class "Default")
      (node (ref "DD2") (pin "3") (pinfunction "IO,_LVDS13p_(CLKUSR)/(DQ1L1)_3") (pintype "bidirectional"))
      (node (ref "XP1") (pin "27") (pinfunction "27_27") (pintype "passive"))
    )
    (net (code "7") (name "/Pin4") (class "Default")
      (node (ref "DD2") (pin "4") (pinfunction "IO,_LVDS13n_4") (pintype "bidirectional"))
      (node (ref "XP1") (pin "28") (pinfunction "28_28") (pintype "passive"))
    )
    (net (code "8") (name "/Pin5") (class "Default")
      (node (ref "DD2") (pin "5") (pinfunction "IO,_VREF0B1_5") (pintype "bidirectional"))
      (node (ref "XP1") (pin "24") (pinfunction "24_24") (pintype "passive"))
    )
    (net (code "9") (name "/Pin6") (class "Default")
      (node (ref "DD2") (pin "6") (pinfunction "IO_(DQ1L2)_6") (pintype "bidirectional"))
      (node (ref "XP1") (pin "23") (pinfunction "23_23") (pintype "passive"))
    )
    (net (code "10") (name "/Pin7") (class "Default")
      (node (ref "DD2") (pin "7") (pinfunction "IO,_LVDS12p_(DQ1L3)_7") (pintype "bidirectional"))
      (node (ref "XP1") (pin "22") (pinfunction "22_22") (pintype "passive"))
    )
    (net (code "11") (name "/Pin10") (class "Default")
      (node (ref "DD2") (pin "10") (pinfunction "IO,_DPCLK1_10") (pintype "bidirectional"))
      (node (ref "XP1") (pin "21") (pinfunction "21_21") (pintype "passive"))
    )
    (net (code "12") (name "/Pin11") (class "Default")
      (node (ref "DD2") (pin "11") (pinfunction "IO,_VREF1B1_11") (pintype "bidirectional"))
      (node (ref "XP1") (pin "19") (pinfunction "19_19") (pintype "passive"))
    )
    (net (code "13") (name "/Pin12") (class "Default")
      (node (ref "DD2") (pin "12") (pinfunction "IO_(nCSO)_12") (pintype "bidirectional"))
      (node (ref "DS1") (pin "1") (pinfunction "nCS_1") (pintype "input"))
      (node (ref "XP3") (pin "8") (pinfunction "8_8") (pintype "passive"))
    )
    (net (code "14") (name "/Pin25") (class "Default")
      (node (ref "DD2") (pin "25") (pinfunction "IO_(ASDO)_25") (pintype "bidirectional"))
      (node (ref "DS1") (pin "5") (pinfunction "ASDI_5") (pintype "input"))
      (node (ref "XP3") (pin "9") (pinfunction "9_9") (pintype "passive"))
    )
    (net (code "15") (name "/Pin26") (class "Default")
      (node (ref "DD2") (pin "26") (pinfunction "IO,_PLL1_OUTp_26") (pintype "bidirectional"))
      (node (ref "XP1") (pin "15") (pinfunction "15_15") (pintype "passive"))
    )
    (net (code "16") (name "/Pin27") (class "Default")
      (node (ref "DD2") (pin "27") (pinfunction "IO,_PLL1_OUTn_27") (pintype "bidirectional"))
      (node (ref "XP1") (pin "16") (pinfunction "16_16") (pintype "passive"))
    )
    (net (code "17") (name "/Pin28") (class "Default")
      (node (ref "DD2") (pin "28") (pinfunction "IO,_DPCLK0_(DQS1L)_28") (pintype "bidirectional"))
      (node (ref "XP1") (pin "13") (pinfunction "13_13") (pintype "passive"))
    )
    (net (code "18") (name "/Pin31") (class "Default")
      (node (ref "DD2") (pin "31") (pinfunction "IO,_VREF2B1_31") (pintype "bidirectional"))
      (node (ref "XP1") (pin "14") (pinfunction "14_14") (pintype "passive"))
    )
    (net (code "19") (name "/Pin32") (class "Default")
      (node (ref "DD2") (pin "32") (pinfunction "IO_(DQ1L4)_32") (pintype "bidirectional"))
      (node (ref "XP1") (pin "11") (pinfunction "11_11") (pintype "passive"))
    )
    (net (code "20") (name "/Pin33") (class "Default")
      (node (ref "DD2") (pin "33") (pinfunction "IO,_LVDS1p_(DQ1L5)_33") (pintype "bidirectional"))
      (node (ref "XP1") (pin "12") (pinfunction "12_12") (pintype "passive"))
    )
    (net (code "21") (name "/Pin34") (class "Default")
      (node (ref "DD2") (pin "34") (pinfunction "IO,_LVDS1n_(DQ1L6)_34") (pintype "bidirectional"))
      (node (ref "XP1") (pin "8") (pinfunction "8_8") (pintype "passive"))
    )
    (net (code "22") (name "/Pin35") (class "Default")
      (node (ref "DD2") (pin "35") (pinfunction "IO,_LVDS0p_(DQ1L7)_35") (pintype "bidirectional"))
      (node (ref "XP1") (pin "7") (pinfunction "7_7") (pintype "passive"))
    )
    (net (code "23") (name "/Pin36") (class "Default")
      (node (ref "DD2") (pin "36") (pinfunction "IO,_LVDS0n_36") (pintype "bidirectional"))
      (node (ref "XP1") (pin "5") (pinfunction "5_5") (pintype "passive"))
    )
    (net (code "24") (name "/Pin37") (class "Default")
      (node (ref "DD2") (pin "37") (pinfunction "IO,_LVDS71p_37") (pintype "bidirectional"))
      (node (ref "XP6") (pin "31") (pinfunction "31_31") (pintype "passive"))
    )
    (net (code "25") (name "/Pin38") (class "Default")
      (node (ref "DD2") (pin "38") (pinfunction "IO,_LVDS71n_38") (pintype "bidirectional"))
      (node (ref "XP6") (pin "32") (pinfunction "32_32") (pintype "passive"))
    )
    (net (code "26") (name "/Pin39") (class "Default")
      (node (ref "DD2") (pin "39") (pinfunction "IO,_LVDS69p_(DQ1B7)_39") (pintype "bidirectional"))
      (node (ref "XP6") (pin "29") (pinfunction "29_29") (pintype "passive"))
    )
    (net (code "27") (name "/Pin40") (class "Default")
      (node (ref "DD2") (pin "40") (pinfunction "IO,_LVDS69n_(DQ1B6)_40") (pintype "bidirectional"))
      (node (ref "XP6") (pin "30") (pinfunction "30_30") (pintype "passive"))
    )
    (net (code "28") (name "/Pin41") (class "Default")
      (node (ref "DD2") (pin "41") (pinfunction "IO,_LVDS68p_(DQ1B5)_41") (pintype "bidirectional"))
      (node (ref "XP6") (pin "27") (pinfunction "27_27") (pintype "passive"))
    )
    (net (code "29") (name "/Pin42") (class "Default")
      (node (ref "DD2") (pin "42") (pinfunction "IO,_LVDS68n_(DQ1B4)_42") (pintype "bidirectional"))
      (node (ref "XP6") (pin "28") (pinfunction "28_28") (pintype "passive"))
    )
    (net (code "30") (name "/Pin47") (class "Default")
      (node (ref "DD2") (pin "47") (pinfunction "IO,_DPCLK7_(DQS1B)_47") (pintype "bidirectional"))
      (node (ref "XP6") (pin "24") (pinfunction "24_24") (pintype "passive"))
    )
    (net (code "31") (name "/Pin48") (class "Default")
      (node (ref "DD2") (pin "48") (pinfunction "IO,_VREF2B4_48") (pintype "bidirectional"))
      (node (ref "XP6") (pin "23") (pinfunction "23_23") (pintype "passive"))
    )
    (net (code "32") (name "/Pin49") (class "Default")
      (node (ref "DD2") (pin "49") (pinfunction "IO,_LVDS67p_49") (pintype "bidirectional"))
      (node (ref "XP6") (pin "22") (pinfunction "22_22") (pintype "passive"))
    )
    (net (code "33") (name "/Pin50") (class "Default")
      (node (ref "DD2") (pin "50") (pinfunction "IO,_LVDS63p_50") (pintype "bidirectional"))
      (node (ref "XP6") (pin "21") (pinfunction "21_21") (pintype "passive"))
    )
    (net (code "34") (name "/Pin51") (class "Default")
      (node (ref "DD2") (pin "51") (pinfunction "IO,_LVDS63n_51") (pintype "bidirectional"))
      (node (ref "XP6") (pin "20") (pinfunction "20_20") (pintype "passive"))
    )
    (net (code "35") (name "/Pin52") (class "Default")
      (node (ref "DD2") (pin "52") (pinfunction "IO,_LVDS62p_52") (pintype "bidirectional"))
      (node (ref "XP6") (pin "19") (pinfunction "19_19") (pintype "passive"))
    )
    (net (code "36") (name "/Pin53") (class "Default")
      (node (ref "DD2") (pin "53") (pinfunction "IO,_LVDS62n_53") (pintype "bidirectional"))
      (node (ref "XP6") (pin "16") (pinfunction "16_16") (pintype "passive"))
    )
    (net (code "37") (name "/Pin56") (class "Default")
      (node (ref "DD2") (pin "56") (pinfunction "IO,_VREF1B4_56") (pintype "bidirectional"))
      (node (ref "XP6") (pin "15") (pinfunction "15_15") (pintype "passive"))
    )
    (net (code "38") (name "/Pin57") (class "Default")
      (node (ref "DD2") (pin "57") (pinfunction "IO,_LVDS61p_(DM1B)_57") (pintype "bidirectional"))
      (node (ref "XP6") (pin "14") (pinfunction "14_14") (pintype "passive"))
    )
    (net (code "39") (name "/Pin58") (class "Default")
      (node (ref "DD2") (pin "58") (pinfunction "IO,_LVDS61n_58") (pintype "bidirectional"))
      (node (ref "XP6") (pin "13") (pinfunction "13_13") (pintype "passive"))
    )
    (net (code "40") (name "/Pin59") (class "Default")
      (node (ref "DD2") (pin "59") (pinfunction "IO,_LVDS59n_59") (pintype "bidirectional"))
      (node (ref "XP6") (pin "12") (pinfunction "12_12") (pintype "passive"))
    )
    (net (code "41") (name "/Pin60") (class "Default")
      (node (ref "DD2") (pin "60") (pinfunction "IO_60") (pintype "bidirectional"))
      (node (ref "XP6") (pin "11") (pinfunction "11_11") (pintype "passive"))
    )
    (net (code "42") (name "/Pin61") (class "Default")
      (node (ref "DD2") (pin "61") (pinfunction "IO,_VREF0B4_61") (pintype "bidirectional"))
      (node (ref "XP6") (pin "8") (pinfunction "8_8") (pintype "passive"))
    )
    (net (code "43") (name "/Pin62") (class "Default")
      (node (ref "DD2") (pin "62") (pinfunction "IO,_DPCLK6_(DQS0B)_62") (pintype "bidirectional"))
      (node (ref "XP6") (pin "7") (pinfunction "7_7") (pintype "passive"))
    )
    (net (code "44") (name "/Pin67") (class "Default")
      (node (ref "DD2") (pin "67") (pinfunction "IO,_LVDS55p_(DQ1B3)_67") (pintype "bidirectional"))
      (node (ref "XP6") (pin "6") (pinfunction "6_6") (pintype "passive"))
    )
    (net (code "45") (name "/Pin68") (class "Default")
      (node (ref "DD2") (pin "68") (pinfunction "IO,_LVDS55n_(DQ1B2)_68") (pintype "bidirectional"))
      (node (ref "XP6") (pin "5") (pinfunction "5_5") (pintype "passive"))
    )
    (net (code "46") (name "/Pin69") (class "Default")
      (node (ref "DD2") (pin "69") (pinfunction "IO,_LVDS54p_(DQ1B1)_69") (pintype "bidirectional"))
      (node (ref "XP6") (pin "4") (pinfunction "4_4") (pintype "passive"))
    )
    (net (code "47") (name "/Pin70") (class "Default")
      (node (ref "DD2") (pin "70") (pinfunction "IO,_LVDS54n_(DQ1B0)_70") (pintype "bidirectional"))
      (node (ref "XP6") (pin "3") (pinfunction "3_3") (pintype "passive"))
    )
    (net (code "48") (name "/Pin71") (class "Default")
      (node (ref "DD2") (pin "71") (pinfunction "IO,_LVDS52p_71") (pintype "bidirectional"))
      (node (ref "HL3") (pin "A") (pinfunction "A_A") (pintype "passive"))
    )
    (net (code "49") (name "/Pin72") (class "Default")
      (node (ref "DD2") (pin "72") (pinfunction "IO,_LVDS52n_72") (pintype "bidirectional"))
      (node (ref "HL2") (pin "A") (pinfunction "A_A") (pintype "passive"))
    )
    (net (code "50") (name "/Pin73") (class "Default")
      (node (ref "DD2") (pin "73") (pinfunction "IO,_LVDS51n_73") (pintype "bidirectional"))
      (node (ref "XP5") (pin "31") (pinfunction "31_31") (pintype "passive"))
    )
    (net (code "51") (name "/Pin74") (class "Default")
      (node (ref "DD2") (pin "74") (pinfunction "IO,_LVDS51p_74") (pintype "bidirectional"))
      (node (ref "XP5") (pin "32") (pinfunction "32_32") (pintype "passive"))
    )
    (net (code "52") (name "/Pin75") (class "Default")
      (node (ref "DD2") (pin "75") (pinfunction "IO,_LVDS50n_75") (pintype "bidirectional"))
      (node (ref "XP5") (pin "29") (pinfunction "29_29") (pintype "passive"))
    )
    (net (code "53") (name "/Pin76") (class "Default")
      (node (ref "DD2") (pin "76") (pinfunction "IO,_LVDS50p_76") (pintype "bidirectional"))
      (node (ref "XP5") (pin "30") (pinfunction "30_30") (pintype "passive"))
    )
    (net (code "54") (name "/Pin77") (class "Default")
      (node (ref "DD2") (pin "77") (pinfunction "IO,_LVDS49n_(DQ1R7)_77") (pintype "bidirectional"))
      (node (ref "XP5") (pin "27") (pinfunction "27_27") (pintype "passive"))
    )
    (net (code "55") (name "/Pin78") (class "Default")
      (node (ref "DD2") (pin "78") (pinfunction "IO,_LVDS49p_(DQ1R6)_78") (pintype "bidirectional"))
      (node (ref "XP5") (pin "28") (pinfunction "28_28") (pintype "passive"))
    )
    (net (code "56") (name "/Pin79") (class "Default")
      (node (ref "DD2") (pin "79") (pinfunction "IO,_VREF2B3_79") (pintype "bidirectional"))
      (node (ref "XP5") (pin "23") (pinfunction "23_23") (pintype "passive"))
    )
    (net (code "57") (name "/Pin82") (class "Default")
      (node (ref "DD2") (pin "82") (pinfunction "IO,_DPCLK5_(DQS1R)_82") (pintype "bidirectional"))
      (node (ref "XP5") (pin "21") (pinfunction "21_21") (pintype "passive"))
    )
    (net (code "58") (name "/Pin83") (class "Default")
      (node (ref "DD2") (pin "83") (pinfunction "IO,_LVDS48n_(DQ1R5)_83") (pintype "bidirectional"))
      (node (ref "XP5") (pin "20") (pinfunction "20_20") (pintype "passive"))
    )
    (net (code "59") (name "/Pin84") (class "Default")
      (node (ref "DD2") (pin "84") (pinfunction "IO,_LVDS48p_(DQ1R4)_84") (pintype "bidirectional"))
      (node (ref "XP5") (pin "19") (pinfunction "19_19") (pintype "passive"))
    )
    (net (code "60") (name "/Pin85") (class "Default")
      (node (ref "DD2") (pin "85") (pinfunction "IO,_LVDS47n_(DM1R)_85") (pintype "bidirectional"))
      (node (ref "XP5") (pin "16") (pinfunction "16_16") (pintype "passive"))
    )
    (net (code "61") (name "/Pin96") (class "Default")
      (node (ref "DD2") (pin "96") (pinfunction "IO,_VREF1B3_96") (pintype "bidirectional"))
      (node (ref "XP5") (pin "15") (pinfunction "15_15") (pintype "passive"))
    )
    (net (code "62") (name "/Pin97") (class "Default")
      (node (ref "DD2") (pin "97") (pinfunction "IO,_LVDS39p_(DQ1R3)_97") (pintype "bidirectional"))
      (node (ref "XP5") (pin "14") (pinfunction "14_14") (pintype "passive"))
    )
    (net (code "63") (name "/Pin98") (class "Default")
      (node (ref "DD2") (pin "98") (pinfunction "IO,_LVDS38n_(DQ1R2)_98") (pintype "bidirectional"))
      (node (ref "XP5") (pin "13") (pinfunction "13_13") (pintype "passive"))
    )
    (net (code "64") (name "/Pin99") (class "Default")
      (node (ref "DD2") (pin "99") (pinfunction "IO,_LVDS38p_(DQ1R1)_99") (pintype "bidirectional"))
      (node (ref "XP5") (pin "12") (pinfunction "12_12") (pintype "passive"))
    )
    (net (code "65") (name "/Pin100") (class "Default")
      (node (ref "DD2") (pin "100") (pinfunction "IO,_DPCLK4_(DQS0R)_100") (pintype "bidirectional"))
      (node (ref "XP5") (pin "11") (pinfunction "11_11") (pintype "passive"))
    )
    (net (code "66") (name "/Pin103") (class "Default")
      (node (ref "DD2") (pin "103") (pinfunction "IO_(DQ1R0)_103") (pintype "bidirectional"))
      (node (ref "XP5") (pin "8") (pinfunction "8_8") (pintype "passive"))
    )
    (net (code "67") (name "/Pin104") (class "Default")
      (node (ref "DD2") (pin "104") (pinfunction "IO,_VREF0B3_104") (pintype "bidirectional"))
      (node (ref "XP5") (pin "7") (pinfunction "7_7") (pintype "passive"))
    )
    (net (code "68") (name "/Pin105") (class "Default")
      (node (ref "DD2") (pin "105") (pinfunction "IO,_LVDS36n_105") (pintype "bidirectional"))
      (node (ref "XP5") (pin "6") (pinfunction "6_6") (pintype "passive"))
    )
    (net (code "69") (name "/Pin106") (class "Default")
      (node (ref "DD2") (pin "106") (pinfunction "IO,_LVDS36p_106") (pintype "bidirectional"))
      (node (ref "XP5") (pin "5") (pinfunction "5_5") (pintype "passive"))
    )
    (net (code "70") (name "/Pin107") (class "Default")
      (node (ref "DD2") (pin "107") (pinfunction "IO,_LVDS35n_107") (pintype "bidirectional"))
      (node (ref "R37") (pin "2") (pinfunction "2_2") (pintype "passive"))
      (node (ref "XP5") (pin "4") (pinfunction "4_4") (pintype "passive"))
    )
    (net (code "71") (name "/Pin108") (class "Default")
      (node (ref "DD2") (pin "108") (pinfunction "IO,_LVDS35p_108") (pintype "bidirectional"))
      (node (ref "R38") (pin "2") (pinfunction "2_2") (pintype "passive"))
      (node (ref "XP5") (pin "3") (pinfunction "3_3") (pintype "passive"))
    )
    (net (code "72") (name "/Pin109") (class "Default")
      (node (ref "DD2") (pin "109") (pinfunction "IO,_LVDS34n_109") (pintype "bidirectional"))
      (node (ref "XP2") (pin "31") (pinfunction "31_31") (pintype "passive"))
    )
    (net (code "73") (name "/Pin110") (class "Default")
      (node (ref "DD2") (pin "110") (pinfunction "IO,_LVDS34p_110") (pintype "bidirectional"))
      (node (ref "XP2") (pin "32") (pinfunction "32_32") (pintype "passive"))
    )
    (net (code "74") (name "/Pin111") (class "Default")
      (node (ref "DD2") (pin "111") (pinfunction "IO,_LVDS32n_(DQ0T0)_111") (pintype "bidirectional"))
      (node (ref "XP2") (pin "29") (pinfunction "29_29") (pintype "passive"))
    )
    (net (code "75") (name "/Pin112") (class "Default")
      (node (ref "DD2") (pin "112") (pinfunction "IO,_LVDS32p_(DQ0T1)_112") (pintype "bidirectional"))
      (node (ref "XP2") (pin "30") (pinfunction "30_30") (pintype "passive"))
    )
    (net (code "76") (name "/Pin113") (class "Default")
      (node (ref "DD2") (pin "113") (pinfunction "IO,_LVDS31n_(DQ0T2)_113") (pintype "bidirectional"))
      (node (ref "XP2") (pin "27") (pinfunction "27_27") (pintype "passive"))
    )
    (net (code "77") (name "/Pin114") (class "Default")
      (node (ref "DD2") (pin "114") (pinfunction "IO,_LVDS31p_(DQ0T3)_114") (pintype "bidirectional"))
      (node (ref "XP2") (pin "28") (pinfunction "28_28") (pintype "passive"))
    )
    (net (code "78") (name "/Pin119") (class "Default")
      (node (ref "DD2") (pin "119") (pinfunction "IO,_DPCLK3_(DQS0T)_119") (pintype "bidirectional"))
      (node (ref "XP2") (pin "23") (pinfunction "23_23") (pintype "passive"))
    )
    (net (code "79") (name "/Pin120") (class "Default")
      (node (ref "DD2") (pin "120") (pinfunction "IO,_VREF0B2_120") (pintype "bidirectional"))
      (node (ref "XP2") (pin "24") (pinfunction "24_24") (pintype "passive"))
    )
    (net (code "80") (name "/Pin121") (class "Default")
      (node (ref "DD2") (pin "121") (pinfunction "IO_121") (pintype "bidirectional"))
      (node (ref "XP2") (pin "21") (pinfunction "21_21") (pintype "passive"))
    )
    (net (code "81") (name "/Pin122") (class "Default")
      (node (ref "DD2") (pin "122") (pinfunction "IO,_LVDS27n_122") (pintype "bidirectional"))
      (node (ref "XP2") (pin "22") (pinfunction "22_22") (pintype "passive"))
    )
    (net (code "82") (name "/Pin123") (class "Default")
      (node (ref "DD2") (pin "123") (pinfunction "IO,_LVDS25n_(DM0T)_123") (pintype "bidirectional"))
      (node (ref "XP2") (pin "19") (pinfunction "19_19") (pintype "passive"))
    )
    (net (code "83") (name "/Pin124") (class "Default")
      (node (ref "DD2") (pin "124") (pinfunction "IO,_LVDS25p_124") (pintype "bidirectional"))
      (node (ref "XP2") (pin "20") (pinfunction "20_20") (pintype "passive"))
    )
    (net (code "84") (name "/Pin125") (class "Default")
      (node (ref "DD2") (pin "125") (pinfunction "IO,_VREF1B2_125") (pintype "bidirectional"))
      (node (ref "XP2") (pin "16") (pinfunction "16_16") (pintype "passive"))
    )
    (net (code "85") (name "/Pin128") (class "Default")
      (node (ref "DD2") (pin "128") (pinfunction "IO,_LVDS24n_128") (pintype "bidirectional"))
      (node (ref "XP2") (pin "15") (pinfunction "15_15") (pintype "passive"))
    )
    (net (code "86") (name "/Pin129") (class "Default")
      (node (ref "DD2") (pin "129") (pinfunction "IO,_LVDS24p_129") (pintype "bidirectional"))
      (node (ref "XP2") (pin "14") (pinfunction "14_14") (pintype "passive"))
    )
    (net (code "87") (name "/Pin130") (class "Default")
      (node (ref "DD2") (pin "130") (pinfunction "IO,_LVDS23n_130") (pintype "bidirectional"))
      (node (ref "XP2") (pin "13") (pinfunction "13_13") (pintype "passive"))
    )
    (net (code "88") (name "/Pin131") (class "Default")
      (node (ref "DD2") (pin "131") (pinfunction "IO,_LVDS23p_131") (pintype "bidirectional"))
      (node (ref "XP2") (pin "12") (pinfunction "12_12") (pintype "passive"))
    )
    (net (code "89") (name "/Pin132") (class "Default")
      (node (ref "DD2") (pin "132") (pinfunction "IO,_LVDS19p_132") (pintype "bidirectional"))
      (node (ref "XP2") (pin "11") (pinfunction "11_11") (pintype "passive"))
    )
    (net (code "90") (name "/Pin133") (class "Default")
      (node (ref "DD2") (pin "133") (pinfunction "IO,_VREF2B2_133") (pintype "bidirectional"))
      (node (ref "XP2") (pin "8") (pinfunction "8_8") (pintype "passive"))
    )
    (net (code "91") (name "/Pin134") (class "Default")
      (node (ref "DD2") (pin "134") (pinfunction "IO,_DPCLK2_(DQS1T)_134") (pintype "bidirectional"))
      (node (ref "XP2") (pin "7") (pinfunction "7_7") (pintype "passive"))
    )
    (net (code "92") (name "/Pin139") (class "Default")
      (node (ref "DD2") (pin "139") (pinfunction "IO,_LVDS18n_(DQ0T4)_139") (pintype "bidirectional"))
      (node (ref "XP2") (pin "6") (pinfunction "6_6") (pintype "passive"))
    )
    (net (code "93") (name "/Pin140") (class "Default")
      (node (ref "DD2") (pin "140") (pinfunction "IO,_LVDS18p_(DQ0T5)_140") (pintype "bidirectional"))
      (node (ref "XP2") (pin "5") (pinfunction "5_5") (pintype "passive"))
    )
    (net (code "94") (name "/Pin141") (class "Default")
      (node (ref "DD2") (pin "141") (pinfunction "IO,_LVDS17n_(DQ0T6)_141") (pintype "bidirectional"))
      (node (ref "XP2") (pin "4") (pinfunction "4_4") (pintype "passive"))
    )
    (net (code "95") (name "/Pin142") (class "Default")
      (node (ref "DD2") (pin "142") (pinfunction "IO,_LVDS17p_(DQ0T7)_142") (pintype "bidirectional"))
      (node (ref "XP2") (pin "3") (pinfunction "3_3") (pintype "passive"))
    )
    (net (code "96") (name "/Pin143") (class "Default")
      (node (ref "DD2") (pin "143") (pinfunction "IO,_LVDS15n_(DEV_OE)_143") (pintype "bidirectional"))
      (node (ref "R3") (pin "2") (pinfunction "2_2") (pintype "passive"))
      (node (ref "SB2") (pin "2") (pinfunction "NO_2") (pintype "passive"))
    )
    (net (code "97") (name "/Pin144") (class "Default")
      (node (ref "DD2") (pin "144") (pinfunction "IO,_LVDS15p_(DEV_CLRn)_144") (pintype "bidirectional"))
      (node (ref "R2") (pin "2") (pinfunction "2_2") (pintype "passive"))
      (node (ref "SB1") (pin "2") (pinfunction "NO_2") (pintype "passive"))
    )
    (net (code "98") (name "/TCK") (class "Default")
      (node (ref "DD2") (pin "88") (pinfunction "TCK_88") (pintype "input"))
      (node (ref "R25") (pin "1") (pinfunction "1_1") (pintype "passive"))
      (node (ref "XP4") (pin "1") (pinfunction "1_1") (pintype "passive"))
    )
    (net (code "99") (name "/TDI") (class "Default")
      (node (ref "DD2") (pin "95") (pinfunction "TDI_95") (pintype "input"))
      (node (ref "R26") (pin "1") (pinfunction "1_1") (pintype "passive"))
      (node (ref "XP4") (pin "9") (pinfunction "9_9") (pintype "passive"))
    )
    (net (code "100") (name "/TDO") (class "Default")
      (node (ref "DD2") (pin "90") (pinfunction "TDO_90") (pintype "output"))
      (node (ref "R29") (pin "1") (pinfunction "1_1") (pintype "passive"))
      (node (ref "XP4") (pin "3") (pinfunction "3_3") (pintype "passive"))
    )
    (net (code "101") (name "/TMS") (class "Default")
      (node (ref "DD2") (pin "89") (pinfunction "TMS_89") (pintype "input"))
      (node (ref "R27") (pin "1") (pinfunction "1_1") (pintype "passive"))
      (node (ref "XP4") (pin "5") (pinfunction "5_5") (pintype "passive"))
    )
    (net (code "102") (name "/USB-RX") (class "Default")
      (node (ref "DA3") (pin "25") (pinfunction "RXD_25") (pintype "passive"))
      (node (ref "HL5") (pin "K") (pinfunction "K_K") (pintype "passive"))
      (node (ref "R38") (pin "1") (pinfunction "1_1") (pintype "passive"))
    )
    (net (code "103") (name "/USB-TX") (class "Default")
      (node (ref "DA3") (pin "26") (pinfunction "TXD_26") (pintype "passive"))
      (node (ref "HL4") (pin "K") (pinfunction "K_K") (pintype "passive"))
      (node (ref "R37") (pin "1") (pinfunction "1_1") (pintype "passive"))
    )
    (net (code "104") (name "CLK_1") (class "Default")
      (node (ref "Q1") (pin "3") (pinfunction "Out_3") (pintype "passive"))
      (node (ref "R19") (pin "1") (pinfunction "1_1") (pintype "passive"))
    )
    (net (code "105") (name "CLK_2") (class "Default")
      (node (ref "R20") (pin "1") (pinfunction "1_1") (pintype "passive"))
    )
    (net (code "106") (name "CLK_3") (class "Default")
      (node (ref "R21") (pin "1") (pinfunction "1_1") (pintype "passive"))
    )
    (net (code "107") (name "CLK_4") (class "Default")
      (node (ref "DD3") (pin "4") (pinfunction "2Y_4") (pintype "passive"))
      (node (ref "R22") (pin "1") (pinfunction "1_1") (pintype "passive"))
    )
    (net (code "108") (name "CLK_5") (class "Default")
      (node (ref "DD3") (pin "8") (pinfunction "4Y_8") (pintype "passive"))
      (node (ref "X1") (pin "1") (pinfunction "1_1") (pintype "passive"))
    )
    (net (code "109") (name "GND") (class "Default")
      (node (ref "C1") (pin "1") (pinfunction "1_1") (pintype "passive"))
      (node (ref "C11") (pin "1") (pinfunction "1_1") (pintype "passive"))
      (node (ref "C12") (pin "2") (pinfunction "2_2") (pintype "passive"))
      (node (ref "C13") (pin "2") (pinfunction "2_2") (pintype "passive"))
      (node (ref "C14") (pin "1") (pinfunction "1_1") (pintype "passive"))
      (node (ref "C15") (pin "2") (pinfunction "2_2") (pintype "passive"))
      (node (ref "C16") (pin "2") (pinfunction "2_2") (pintype "passive"))
      (node (ref "C17") (pin "2") (pinfunction "2_2") (pintype "passive"))
      (node (ref "C18") (pin "2") (pinfunction "2_2") (pintype "passive"))
      (node (ref "C19") (pin "2") (pinfunction "2_2") (pintype "passive"))
      (node (ref "C20") (pin "2") (pinfunction "2_2") (pintype "passive"))
      (node (ref "C21") (pin "2") (pinfunction "2_2") (pintype "passive"))
      (node (ref "C22") (pin "2") (pinfunction "2_2") (pintype "passive"))
      (node (ref "C23") (pin "2") (pinfunction "2_2") (pintype "passive"))
      (node (ref "C24") (pin "2") (pinfunction "2_2") (pintype "passive"))
      (node (ref "C25") (pin "2") (pinfunction "2_2") (pintype "passive"))
      (node (ref "C26") (pin "2") (pinfunction "2_2") (pintype "passive"))
      (node (ref "C27") (pin "2") (pinfunction "2_2") (pintype "passive"))
      (node (ref "C28") (pin "2") (pinfunction "2_2") (pintype "passive"))
      (node (ref "C29") (pin "2") (pinfunction "2_2") (pintype "passive"))
      (node (ref "C30") (pin "2") (pinfunction "2_2") (pintype "passive"))
      (node (ref "C31") (pin "2") (pinfunction "2_2") (pintype "passive"))
      (node (ref "C32") (pin "2") (pinfunction "2_2") (pintype "passive"))
      (node (ref "C33") (pin "2") (pinfunction "2_2") (pintype "passive"))
      (node (ref "C34") (pin "2") (pinfunction "2_2") (pintype "passive"))
      (node (ref "C35") (pin "2") (pinfunction "2_2") (pintype "passive"))
      (node (ref "C36") (pin "1") (pinfunction "1_1") (pintype "passive"))
      (node (ref "C37") (pin "1") (pinfunction "1_1") (pintype "passive"))
      (node (ref "C38") (pin "2") (pinfunction "2_2") (pintype "passive"))
      (node (ref "C39") (pin "2") (pinfunction "2_2") (pintype "passive"))
      (node (ref "C40") (pin "1") (pinfunction "1_1") (pintype "passive"))
      (node (ref "C41") (pin "1") (pinfunction "1_1") (pintype "passive"))
      (node (ref "C43") (pin "1") (pinfunction "1_1") (pintype "passive"))
      (node (ref "C45") (pin "1") (pinfunction "1_1") (pintype "passive"))
      (node (ref "C46") (pin "1") (pinfunction "1_1") (pintype "passive"))
      (node (ref "C47") (pin "1") (pinfunction "1_1") (pintype "passive"))
      (node (ref "C5") (pin "1") (pinfunction "1_1") (pintype "passive"))
      (node (ref "C50") (pin "1") (pinfunction "1_1") (pintype "passive"))
      (node (ref "C51") (pin "1") (pinfunction "1_1") (pintype "passive"))
      (node (ref "C52") (pin "1") (pinfunction "1_1") (pintype "passive"))
      (node (ref "C53") (pin "1") (pinfunction "1_1") (pintype "passive"))
      (node (ref "C54") (pin "1") (pinfunction "1_1") (pintype "passive"))
      (node (ref "C55") (pin "1") (pinfunction "1_1") (pintype "passive"))
      (node (ref "C56") (pin "1") (pinfunction "1_1") (pintype "passive"))
      (node (ref "C7") (pin "1") (pinfunction "1_1") (pintype "passive"))
      (node (ref "C8") (pin "1") (pinfunction "1_1") (pintype "passive"))
      (node (ref "C9") (pin "1") (pinfunction "1_1") (pintype "passive"))
      (node (ref "DA1") (pin "1") (pinfunction "Gnd_1") (pintype "passive"))
      (node (ref "DA2") (pin "1") (pinfunction "Gnd_1") (pintype "passive"))
      (node (ref "DA3") (pin "3") (pinfunction "GND_3") (pintype "passive"))
      (node (ref "DD2") (pin "101") (pinfunction "GND_101") (pintype "power_in"))
      (node (ref "DD2") (pin "116") (pinfunction "GND_116") (pintype "power_in"))
      (node (ref "DD2") (pin "118") (pinfunction "GND_118") (pintype "power_in"))
      (node (ref "DD2") (pin "127") (pinfunction "GND_127") (pintype "power_in"))
      (node (ref "DD2") (pin "136") (pinfunction "GND_136") (pintype "power_in"))
      (node (ref "DD2") (pin "138") (pinfunction "GND_138") (pintype "power_in"))
      (node (ref "DD2") (pin "18") (pinfunction "GNDA_PLL1_18") (pintype "power_in"))
      (node (ref "DD2") (pin "19") (pinfunction "GNDG_PLL1_19") (pintype "power_in"))
      (node (ref "DD2") (pin "22") (pinfunction "MSEL0_22") (pintype "input"))
      (node (ref "DD2") (pin "23") (pinfunction "MSEL1_23") (pintype "input"))
      (node (ref "DD2") (pin "30") (pinfunction "GND_30") (pintype "power_in"))
      (node (ref "DD2") (pin "43") (pinfunction "GND_43") (pintype "power_in"))
      (node (ref "DD2") (pin "45") (pinfunction "GND_45") (pintype "power_in"))
      (node (ref "DD2") (pin "54") (pinfunction "GND_54") (pintype "power_in"))
      (node (ref "DD2") (pin "63") (pinfunction "GND_63") (pintype "power_in"))
      (node (ref "DD2") (pin "65") (pinfunction "GND_65") (pintype "power_in"))
      (node (ref "DD2") (pin "80") (pinfunction "GND_80") (pintype "power_in"))
      (node (ref "DD2") (pin "9") (pinfunction "GND_9") (pintype "power_in"))
      (node (ref "DD2") (pin "91") (pinfunction "GNDG_PLL2_91") (pintype "power_in"))
      (node (ref "DD3") (pin "7") (pinfunction "GND_7") (pintype "power_in"))
      (node (ref "DS1") (pin "4") (pinfunction "GND_4") (pintype "power_in"))
      (node (ref "HL1") (pin "K") (pinfunction "K_K") (pintype "passive"))
      (node (ref "HL2") (pin "K") (pinfunction "K_K") (pintype "passive"))
      (node (ref "HL3") (pin "K") (pinfunction "K_K") (pintype "passive"))
      (node (ref "Q1") (pin "2") (pinfunction "Gnd_2") (pintype "passive"))
      (node (ref "R18") (pin "2") (pinfunction "2_2") (pintype "passive"))
      (node (ref "R2") (pin "1") (pinfunction "1_1") (pintype "passive"))
      (node (ref "R25") (pin "2") (pinfunction "2_2") (pintype "passive"))
      (node (ref "R3") (pin "1") (pinfunction "1_1") (pintype "passive"))
      (node (ref "R34") (pin "1") (pinfunction "1_1") (pintype "passive"))
      (node (ref "R35") (pin "2") (pinfunction "2_2") (pintype "passive"))
      (node (ref "R36") (pin "2") (pinfunction "2_2") (pintype "passive"))
      (node (ref "XP1") (pin "10") (pinfunction "10_10") (pintype "passive"))
      (node (ref "XP1") (pin "18") (pinfunction "18_18") (pintype "passive"))
      (node (ref "XP1") (pin "2") (pinfunction "2_2") (pintype "passive"))
      (node (ref "XP1") (pin "26") (pinfunction "26_26") (pintype "passive"))
      (node (ref "XP1") (pin "34") (pinfunction "34_34") (pintype "passive"))
      (node (ref "XP2") (pin "10") (pinfunction "10_10") (pintype "passive"))
      (node (ref "XP2") (pin "18") (pinfunction "18_18") (pintype "passive"))
      (node (ref "XP2") (pin "2") (pinfunction "2_2") (pintype "passive"))
      (node (ref "XP2") (pin "26") (pinfunction "26_26") (pintype "passive"))
      (node (ref "XP2") (pin "34") (pinfunction "34_34") (pintype "passive"))
      (node (ref "XP3") (pin "10") (pinfunction "10_10") (pintype "passive"))
      (node (ref "XP3") (pin "2") (pinfunction "2_2") (pintype "passive"))
      (node (ref "XP4") (pin "10") (pinfunction "10_10") (pintype "passive"))
      (node (ref "XP4") (pin "2") (pinfunction "2_2") (pintype "passive"))
      (node (ref "XP5") (pin "10") (pinfunction "10_10") (pintype "passive"))
      (node (ref "XP5") (pin "18") (pinfunction "18_18") (pintype "passive"))
      (node (ref "XP5") (pin "2") (pinfunction "2_2") (pintype "passive"))
      (node (ref "XP5") (pin "26") (pinfunction "26_26") (pintype "passive"))
      (node (ref "XP5") (pin "34") (pinfunction "34_34") (pintype "passive"))
      (node (ref "XP6") (pin "10") (pinfunction "10_10") (pintype "passive"))
      (node (ref "XP6") (pin "18") (pinfunction "18_18") (pintype "passive"))
      (node (ref "XP6") (pin "2") (pinfunction "2_2") (pintype "passive"))
      (node (ref "XP6") (pin "26") (pinfunction "26_26") (pintype "passive"))
      (node (ref "XP6") (pin "34") (pinfunction "34_34") (pintype "passive"))
      (node (ref "XS1") (pin "5") (pinfunction "5_5") (pintype "passive"))
      (node (ref "XS1") (pin "6") (pinfunction "6_6") (pintype "passive"))
    )
    (net (code "110") (name "Net-(C51-Pad2)") (class "Default")
      (node (ref "C51") (pin "2") (pinfunction "2_2") (pintype "passive"))
      (node (ref "C53") (pin "2") (pinfunction "2_2") (pintype "passive"))
    )
    (net (code "111") (name "Net-(C54-Pad2)") (class "Default")
      (node (ref "C54") (pin "2") (pinfunction "2_2") (pintype "passive"))
      (node (ref "G3") (pin "2") (pinfunction "2_2") (pintype "passive"))
      (node (ref "R17") (pin "1") (pinfunction "1_1") (pintype "passive"))
    )
    (net (code "112") (name "Net-(C56-Pad2)") (class "Default")
      (node (ref "C56") (pin "2") (pinfunction "2_2") (pintype "passive"))
      (node (ref "G4") (pin "2") (pinfunction "2_2") (pintype "passive"))
      (node (ref "R40") (pin "1") (pinfunction "1_1") (pintype "passive"))
    )
    (net (code "113") (name "Net-(DA3-D+)") (class "Default")
      (node (ref "DA3") (pin "4") (pinfunction "D+_4") (pintype "passive"))
      (node (ref "XS1") (pin "3") (pinfunction "3_3") (pintype "passive"))
    )
    (net (code "114") (name "Net-(DA3-D-)") (class "Default")
      (node (ref "DA3") (pin "5") (pinfunction "D-_5") (pintype "passive"))
      (node (ref "XS1") (pin "2") (pinfunction "2_2") (pintype "passive"))
    )
    (net (code "115") (name "Net-(DA3-Vdd)") (class "Default")
      (node (ref "C43") (pin "2") (pinfunction "2_2") (pintype "passive"))
      (node (ref "C45") (pin "2") (pinfunction "2_2") (pintype "passive"))
      (node (ref "DA3") (pin "6") (pinfunction "Vdd_6") (pintype "passive"))
    )
    (net (code "116") (name "Net-(DA3-~{RST})") (class "Default")
      (node (ref "DA3") (pin "9") (pinfunction "~{RST}_9") (pintype "passive"))
      (node (ref "R33") (pin "1") (pinfunction "1_1") (pintype "passive"))
    )
    (net (code "117") (name "Net-(DA3-~{su}s)") (class "Default")
      (node (ref "DA3") (pin "11") (pinfunction "~{su}s_11") (pintype "passive"))
      (node (ref "R34") (pin "2") (pinfunction "2_2") (pintype "passive"))
    )
    (net (code "118") (name "Net-(DD2-CLK0,_LVDSCLK1p)") (class "Default")
      (node (ref "DD2") (pin "16") (pinfunction "CLK0,_LVDSCLK1p_16") (pintype "input"))
      (node (ref "R19") (pin "2") (pinfunction "2_2") (pintype "passive"))
    )
    (net (code "119") (name "Net-(DD2-CLK1,_LVDSCLK1n)") (class "Default")
      (node (ref "DD2") (pin "17") (pinfunction "CLK1,_LVDSCLK1n_17") (pintype "input"))
      (node (ref "R20") (pin "2") (pinfunction "2_2") (pintype "passive"))
    )
    (net (code "120") (name "Net-(DD2-CLK2,_LVDSCLK2p)") (class "Default")
      (node (ref "DD2") (pin "93") (pinfunction "CLK2,_LVDSCLK2p_93") (pintype "input"))
      (node (ref "R21") (pin "2") (pinfunction "2_2") (pintype "passive"))
    )
    (net (code "121") (name "Net-(DD2-CLK3,_LVDSCLK2n)") (class "Default")
      (node (ref "DD2") (pin "92") (pinfunction "CLK3,_LVDSCLK2n_92") (pintype "input"))
      (node (ref "R22") (pin "2") (pinfunction "2_2") (pintype "passive"))
    )
    (net (code "122") (name "Net-(DD2-DATA0)") (class "Default")
      (node (ref "DD2") (pin "13") (pinfunction "DATA0_13") (pintype "input"))
      (node (ref "DS1") (pin "2") (pinfunction "DATA_2") (pintype "output"))
      (node (ref "XP3") (pin "7") (pinfunction "7_7") (pintype "passive"))
    )
    (net (code "123") (name "Net-(DD2-DCLK)") (class "Default")
      (node (ref "DD2") (pin "24") (pinfunction "DCLK_24") (pintype "bidirectional"))
      (node (ref "DS1") (pin "6") (pinfunction "DCLK_6") (pintype "input"))
      (node (ref "XP3") (pin "1") (pinfunction "1_1") (pintype "passive"))
    )
    (net (code "124") (name "Net-(DD2-VCCA_PLL1)") (class "Default")
      (node (ref "C28") (pin "1") (pinfunction "1_1") (pintype "passive"))
      (node (ref "C32") (pin "1") (pinfunction "1_1") (pintype "passive"))
      (node (ref "DD2") (pin "15") (pinfunction "VCCA_PLL1_15") (pintype "power_in"))
      (node (ref "ZL1") (pin "2") (pinfunction "2_2") (pintype "passive"))
    )
    (net (code "125") (name "Net-(DD2-VCCA_PLL2)") (class "Default")
      (node (ref "C29") (pin "1") (pinfunction "1_1") (pintype "passive"))
      (node (ref "C33") (pin "1") (pinfunction "1_1") (pintype "passive"))
      (node (ref "DD2") (pin "94") (pinfunction "VCCA_PLL2_94") (pintype "power_in"))
      (node (ref "ZL2") (pin "2") (pinfunction "2_2") (pintype "passive"))
    )
    (net (code "126") (name "Net-(DD2-nCE)") (class "Default")
      (node (ref "DD2") (pin "21") (pinfunction "nCE_21") (pintype "input"))
      (node (ref "R18") (pin "1") (pinfunction "1_1") (pintype "passive"))
      (node (ref "XP3") (pin "6") (pinfunction "6_6") (pintype "passive"))
    )
    (net (code "127") (name "Net-(DD2-nCONFIG)") (class "Default")
      (node (ref "DD2") (pin "14") (pinfunction "nCONFIG_14") (pintype "input"))
      (node (ref "R15") (pin "1") (pinfunction "1_1") (pintype "passive"))
      (node (ref "XP3") (pin "5") (pinfunction "5_5") (pintype "passive"))
    )
    (net (code "128") (name "Net-(DD2-nSTATUS)") (class "Default")
      (node (ref "DD2") (pin "87") (pinfunction "nSTATUS_87") (pintype "bidirectional"))
      (node (ref "R23") (pin "1") (pinfunction "1_1") (pintype "passive"))
    )
    (net (code "129") (name "Net-(DD3A-1A)") (class "Default")
      (node (ref "C14") (pin "2") (pinfunction "2_2") (pintype "passive"))
      (node (ref "DD3") (pin "1") (pinfunction "1A_1") (pintype "passive"))
      (node (ref "G3") (pin "1") (pinfunction "1_1") (pintype "passive"))
      (node (ref "R16") (pin "1") (pinfunction "1_1") (pintype "passive"))
    )
    (net (code "130") (name "Net-(DD3A-1Y)") (class "Default")
      (node (ref "DD3") (pin "2") (pinfunction "1Y_2") (pintype "passive"))
      (node (ref "DD3") (pin "3") (pinfunction "2A_3") (pintype "passive"))
      (node (ref "R16") (pin "2") (pinfunction "2_2") (pintype "passive"))
      (node (ref "R17") (pin "2") (pinfunction "2_2") (pintype "passive"))
    )
    (net (code "131") (name "Net-(DD3C-3A)") (class "Default")
      (node (ref "C55") (pin "2") (pinfunction "2_2") (pintype "passive"))
      (node (ref "DD3") (pin "5") (pinfunction "3A_5") (pintype "passive"))
      (node (ref "G4") (pin "1") (pinfunction "1_1") (pintype "passive"))
      (node (ref "R39") (pin "1") (pinfunction "1_1") (pintype "passive"))
    )
    (net (code "132") (name "Net-(DD3C-3Y)") (class "Default")
      (node (ref "DD3") (pin "6") (pinfunction "3Y_6") (pintype "passive"))
      (node (ref "DD3") (pin "9") (pinfunction "4A_9") (pintype "passive"))
      (node (ref "R39") (pin "2") (pinfunction "2_2") (pintype "passive"))
      (node (ref "R40") (pin "2") (pinfunction "2_2") (pintype "passive"))
    )
    (net (code "133") (name "Net-(DD3E-5A)") (class "Default")
      (node (ref "DD3") (pin "11") (pinfunction "5A_11") (pintype "passive"))
      (node (ref "X3") (pin "1") (pinfunction "1_1") (pintype "passive"))
    )
    (net (code "134") (name "Net-(DD3E-5Y)") (class "Default")
      (node (ref "DD3") (pin "10") (pinfunction "5Y_10") (pintype "passive"))
      (node (ref "X2") (pin "1") (pinfunction "1_1") (pintype "passive"))
    )
    (net (code "135") (name "Net-(DD3F-6A)") (class "Default")
      (node (ref "DD3") (pin "13") (pinfunction "6A_13") (pintype "passive"))
      (node (ref "X5") (pin "1") (pinfunction "1_1") (pintype "passive"))
    )
    (net (code "136") (name "Net-(DD3F-6Y)") (class "Default")
      (node (ref "DD3") (pin "12") (pinfunction "6Y_12") (pintype "passive"))
      (node (ref "X4") (pin "1") (pinfunction "1_1") (pintype "passive"))
    )
    (net (code "137") (name "Net-(HL1-PadA)") (class "Default")
      (node (ref "HL1") (pin "A") (pinfunction "A_A") (pintype "passive"))
      (node (ref "R24") (pin "1") (pinfunction "1_1") (pintype "passive"))
    )
    (net (code "138") (name "Net-(HL4-PadA)") (class "Default")
      (node (ref "HL4") (pin "A") (pinfunction "A_A") (pintype "passive"))
      (node (ref "R35") (pin "1") (pinfunction "1_1") (pintype "passive"))
    )
    (net (code "139") (name "Net-(HL5-PadA)") (class "Default")
      (node (ref "HL5") (pin "A") (pinfunction "A_A") (pintype "passive"))
      (node (ref "R36") (pin "1") (pinfunction "1_1") (pintype "passive"))
    )
    (net (code "140") (name "Net-(Q1-OE)") (class "Default")
      (node (ref "Q1") (pin "1") (pinfunction "OE_1") (pintype "passive"))
      (node (ref "R1") (pin "2") (pinfunction "2_2") (pintype "passive"))
    )
    (net (code "141") (name "Net-(XS1-Pad1)") (class "Default")
      (node (ref "XS1") (pin "1") (pinfunction "1_1") (pintype "passive"))
      (node (ref "ZL3") (pin "1") (pinfunction "1_1") (pintype "passive"))
    )
    (net (code "142") (name "nReset") (class "Default")
      (node (ref "DD2") (pin "86") (pinfunction "CONF_DONE_86") (pintype "bidirectional"))
      (node (ref "R14") (pin "1") (pinfunction "1_1") (pintype "passive"))
      (node (ref "XP3") (pin "3") (pinfunction "3_3") (pintype "passive"))
    )
    (net (code "143") (name "unconnected-(DA3-CTS-Pad23)") (class "Default")
      (node (ref "DA3") (pin "23") (pinfunction "CTS_23") (pintype "passive"))
    )
    (net (code "144") (name "unconnected-(DA3-DCD-Pad1)") (class "Default")
      (node (ref "DA3") (pin "1") (pinfunction "DCD_1") (pintype "passive"))
    )
    (net (code "145") (name "unconnected-(DA3-DSR-Pad27)") (class "Default")
      (node (ref "DA3") (pin "27") (pinfunction "DSR_27") (pintype "passive"))
    )
    (net (code "146") (name "unconnected-(DA3-DTR-Pad28)") (class "Default")
      (node (ref "DA3") (pin "28") (pinfunction "DTR_28") (pintype "passive"))
    )
    (net (code "147") (name "unconnected-(DA3-NC-Pad10)") (class "Default")
      (node (ref "DA3") (pin "10") (pinfunction "NC_10") (pintype "passive+no_connect"))
    )
    (net (code "148") (name "unconnected-(DA3-NC-Pad13)") (class "Default")
      (node (ref "DA3") (pin "13") (pinfunction "NC_13") (pintype "passive+no_connect"))
    )
    (net (code "149") (name "unconnected-(DA3-NC-Pad14)") (class "Default")
      (node (ref "DA3") (pin "14") (pinfunction "NC_14") (pintype "passive+no_connect"))
    )
    (net (code "150") (name "unconnected-(DA3-NC-Pad15)") (class "Default")
      (node (ref "DA3") (pin "15") (pinfunction "NC_15") (pintype "passive+no_connect"))
    )
    (net (code "151") (name "unconnected-(DA3-NC-Pad16)") (class "Default")
      (node (ref "DA3") (pin "16") (pinfunction "NC_16") (pintype "passive+no_connect"))
    )
    (net (code "152") (name "unconnected-(DA3-NC-Pad17)") (class "Default")
      (node (ref "DA3") (pin "17") (pinfunction "NC_17") (pintype "passive+no_connect"))
    )
    (net (code "153") (name "unconnected-(DA3-NC-Pad18)") (class "Default")
      (node (ref "DA3") (pin "18") (pinfunction "NC_18") (pintype "passive+no_connect"))
    )
    (net (code "154") (name "unconnected-(DA3-NC-Pad22)") (class "Default")
      (node (ref "DA3") (pin "22") (pinfunction "NC_22") (pintype "passive+no_connect"))
    )
    (net (code "155") (name "unconnected-(DA3-RI-Pad2)") (class "Default")
      (node (ref "DA3") (pin "2") (pinfunction "RI_2") (pintype "passive"))
    )
    (net (code "156") (name "unconnected-(DA3-RTS-Pad24)") (class "Default")
      (node (ref "DA3") (pin "24") (pinfunction "RTS_24") (pintype "passive"))
    )
    (net (code "157") (name "unconnected-(DA3-sus-Pad12)") (class "Default")
      (node (ref "DA3") (pin "12") (pinfunction "sus_12") (pintype "passive+no_connect"))
    )
    (net (code "158") (name "unconnected-(DD2-nCEO-Pad20)") (class "Default")
      (node (ref "DD2") (pin "20") (pinfunction "nCEO_20") (pintype "output+no_connect"))
    )
    (net (code "159") (name "unconnected-(XP1-Pad3)") (class "Default")
      (node (ref "XP1") (pin "3") (pinfunction "3_3") (pintype "passive"))
    )
    (net (code "160") (name "unconnected-(XP1-Pad4)") (class "Default")
      (node (ref "XP1") (pin "4") (pinfunction "4_4") (pintype "passive"))
    )
    (net (code "161") (name "unconnected-(XP1-Pad6)") (class "Default")
      (node (ref "XP1") (pin "6") (pinfunction "6_6") (pintype "passive"))
    )
    (net (code "162") (name "unconnected-(XP1-Pad20)") (class "Default")
      (node (ref "XP1") (pin "20") (pinfunction "20_20") (pintype "passive"))
    )
    (net (code "163") (name "unconnected-(XP1-Pad31)") (class "Default")
      (node (ref "XP1") (pin "31") (pinfunction "31_31") (pintype "passive"))
    )
    (net (code "164") (name "unconnected-(XP1-Pad32)") (class "Default")
      (node (ref "XP1") (pin "32") (pinfunction "32_32") (pintype "passive"))
    )
    (net (code "165") (name "unconnected-(XP4-Pad6)") (class "Default")
      (node (ref "XP4") (pin "6") (pinfunction "6_6") (pintype "passive"))
    )
    (net (code "166") (name "unconnected-(XP4-Pad7)") (class "Default")
      (node (ref "XP4") (pin "7") (pinfunction "7_7") (pintype "passive"))
    )
    (net (code "167") (name "unconnected-(XP4-Pad8)") (class "Default")
      (node (ref "XP4") (pin "8") (pinfunction "8_8") (pintype "passive"))
    )
    (net (code "168") (name "unconnected-(XP5-Pad22)") (class "Default")
      (node (ref "XP5") (pin "22") (pinfunction "22_22") (pintype "passive"))
    )
    (net (code "169") (name "unconnected-(XP5-Pad24)") (class "Default")
      (node (ref "XP5") (pin "24") (pinfunction "24_24") (pintype "passive"))
    )
    (net (code "170") (name "unconnected-(XS1-Pad4)") (class "Default")
      (node (ref "XS1") (pin "4") (pinfunction "4_4") (pintype "passive"))
    )
  )
)
